# e-ink-display-v010.net
KiCad netlist of a schematic drawn in EAGLE
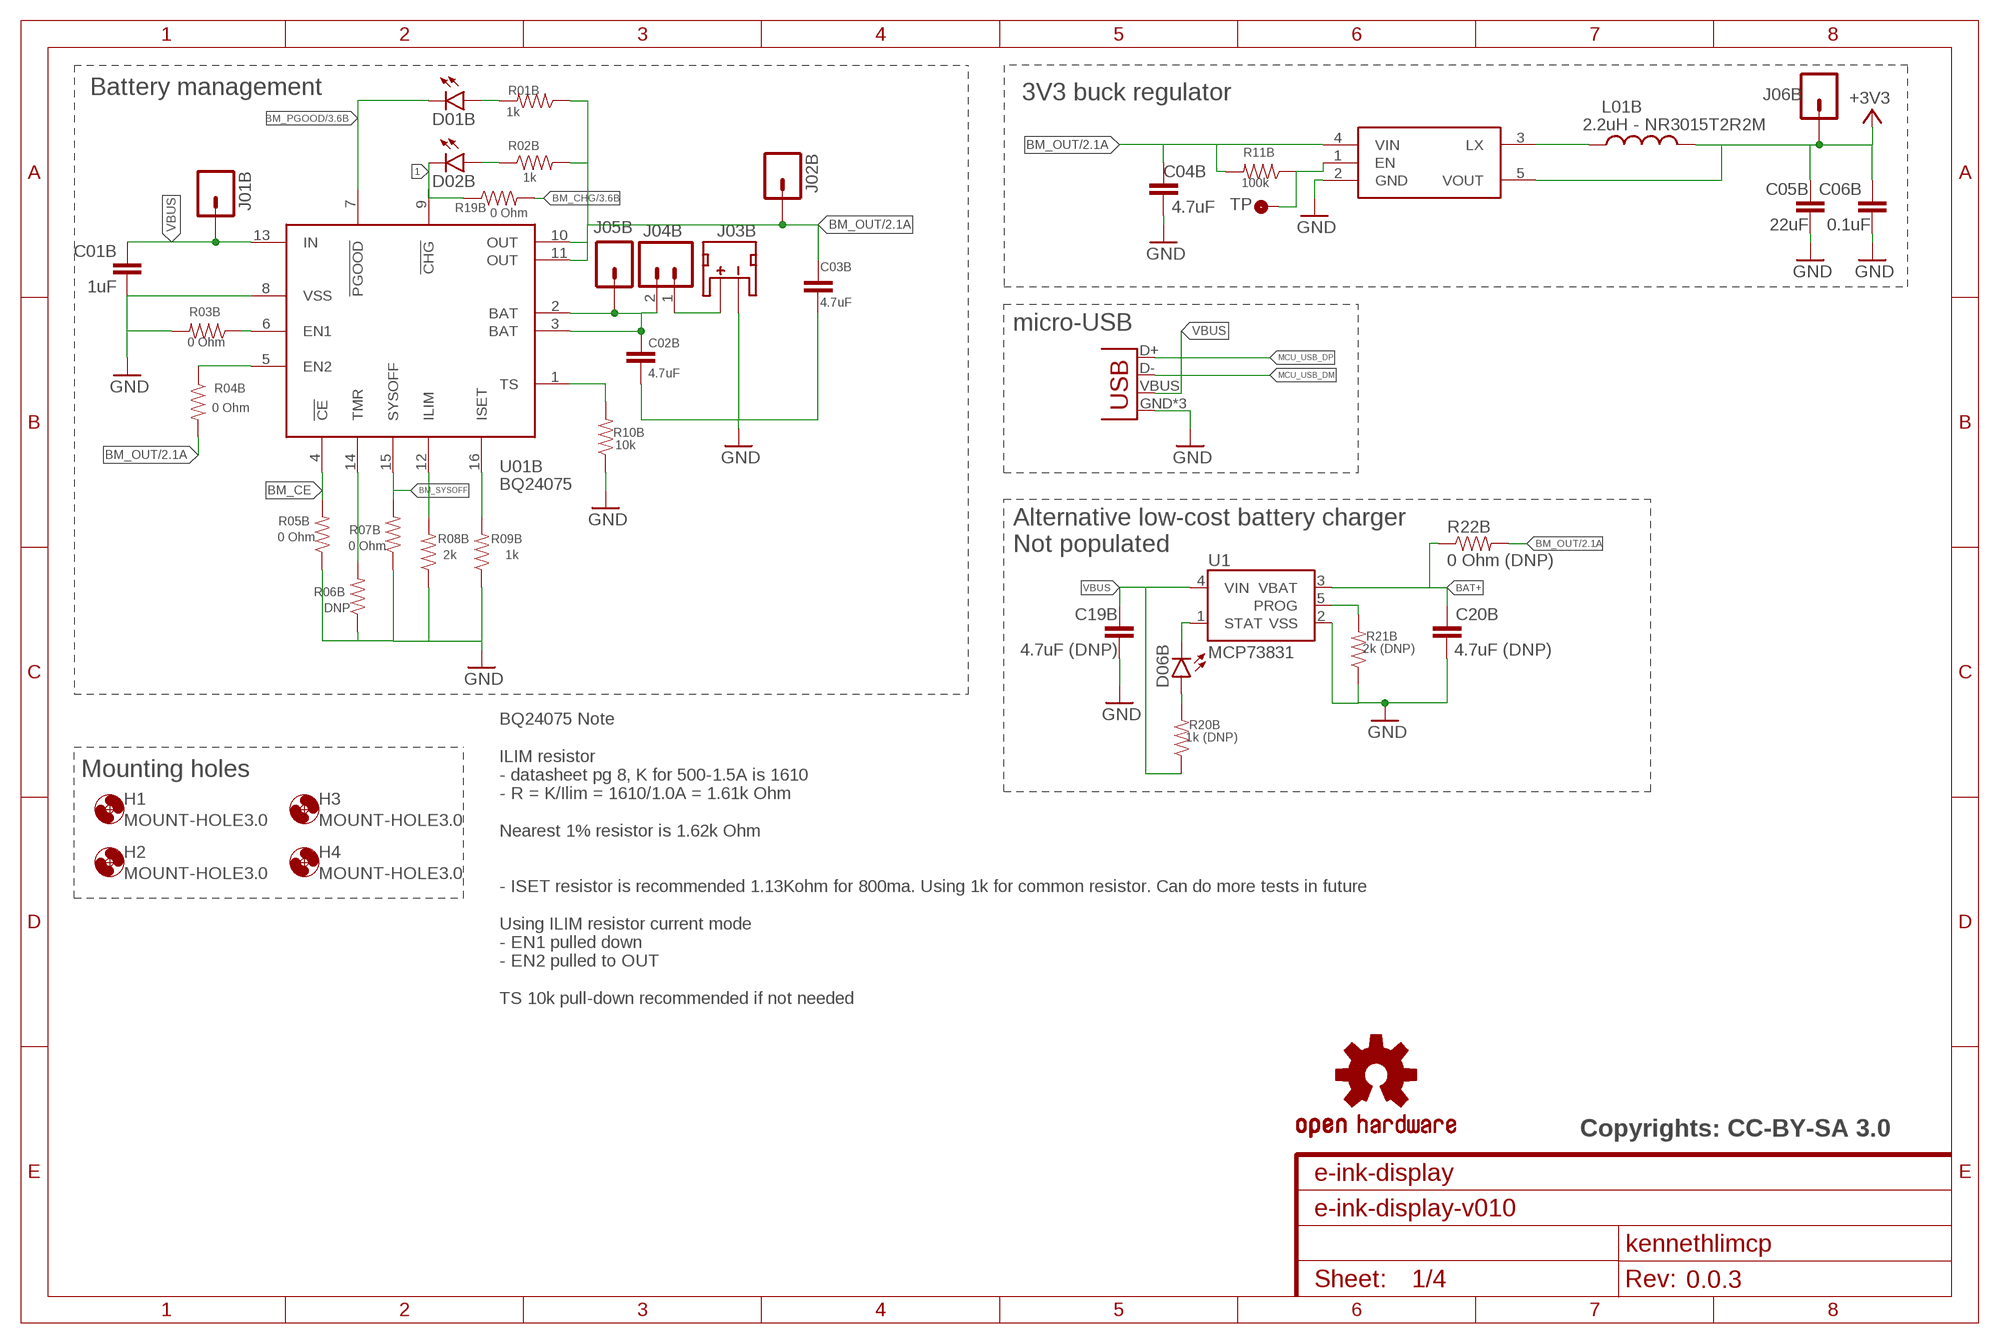
[diagram p0: schematic, sheet 1]
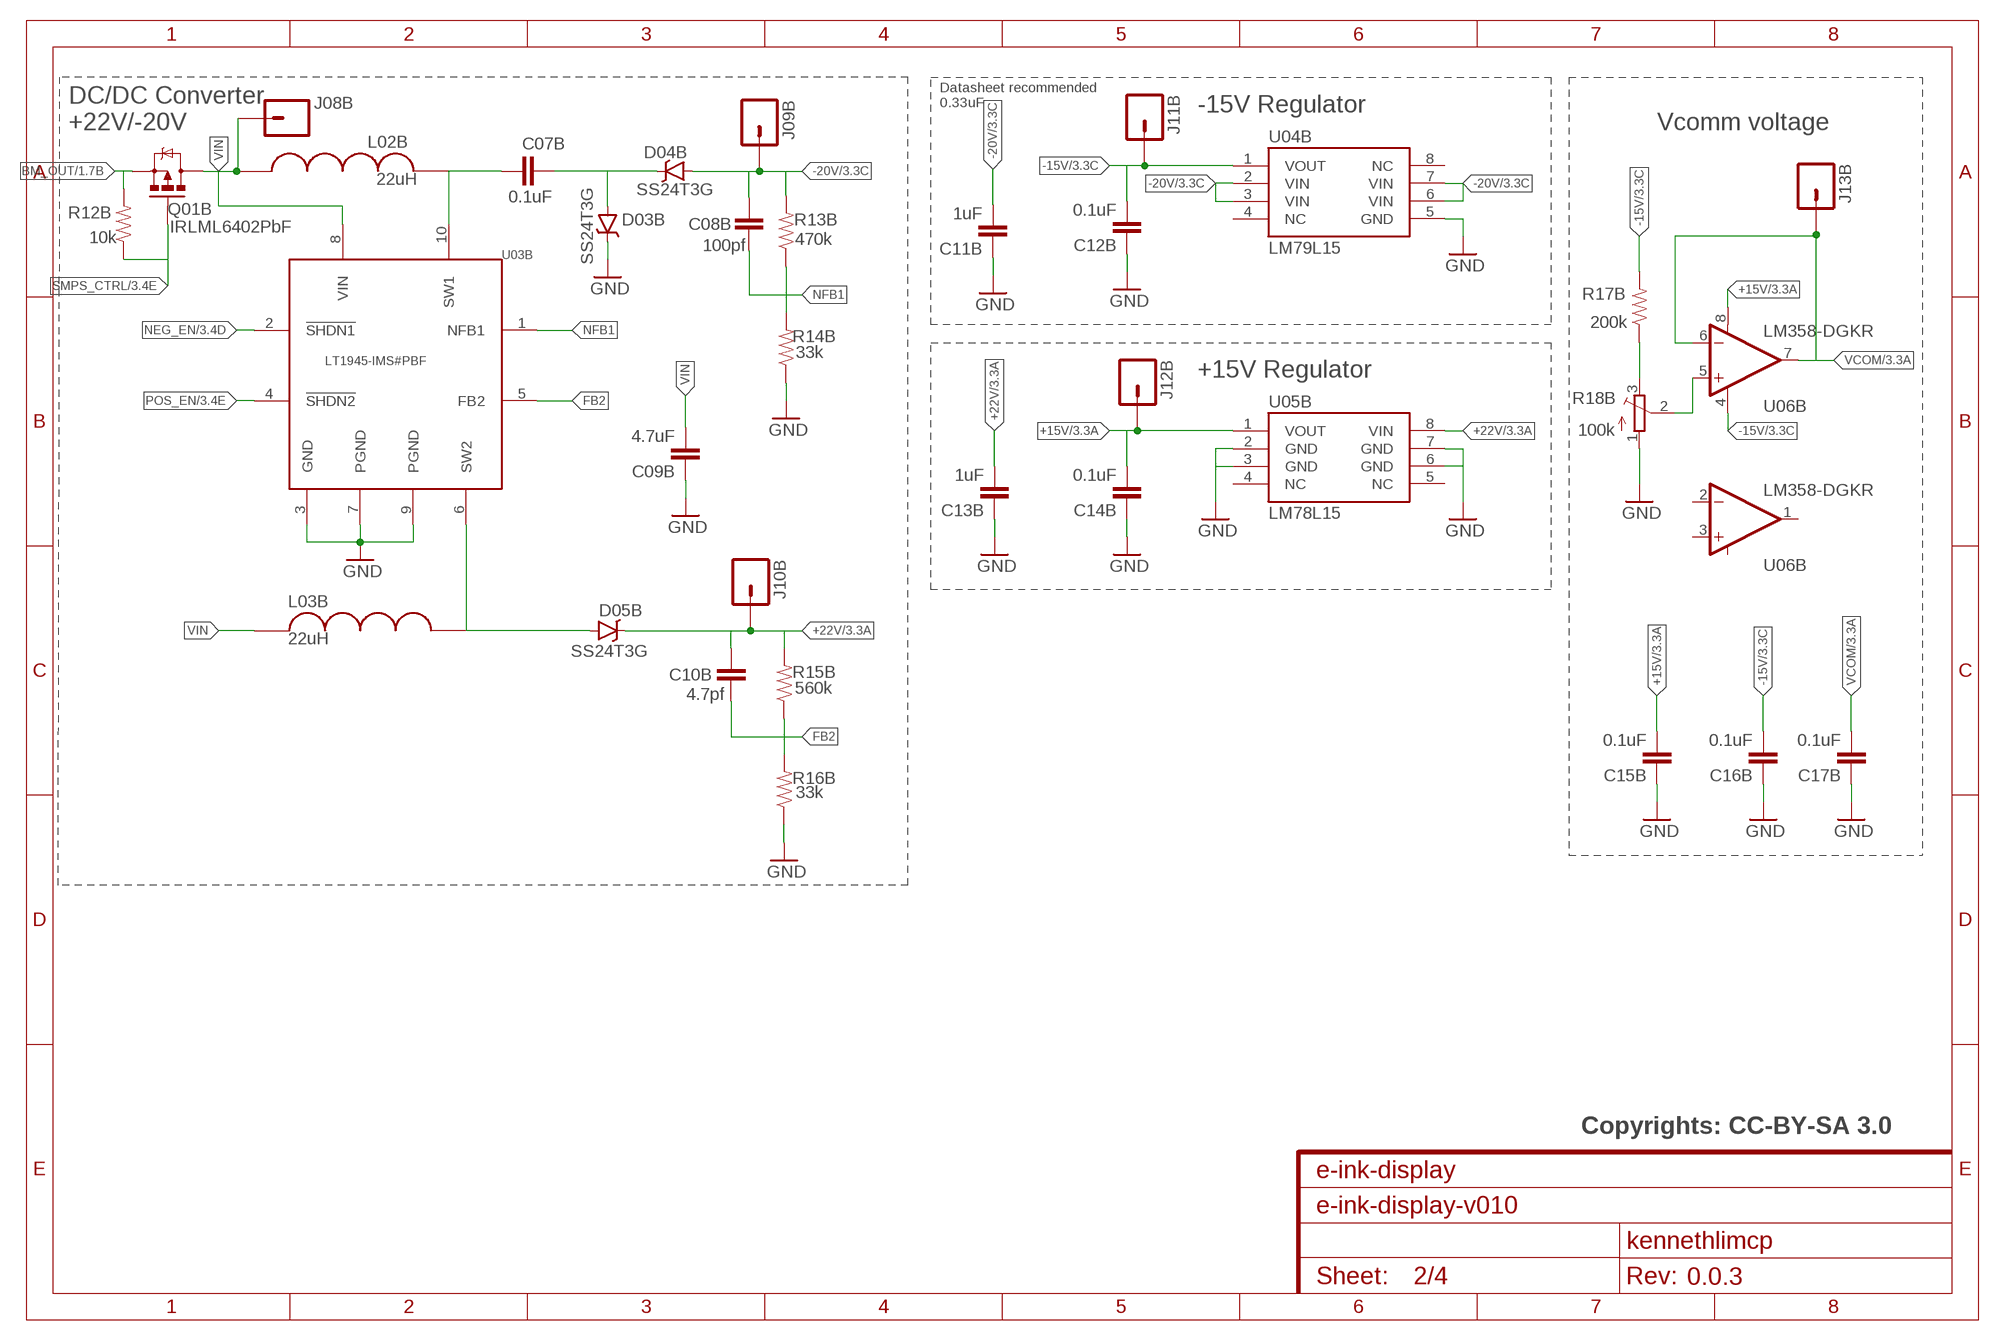
[diagram p1: schematic, sheet 2]
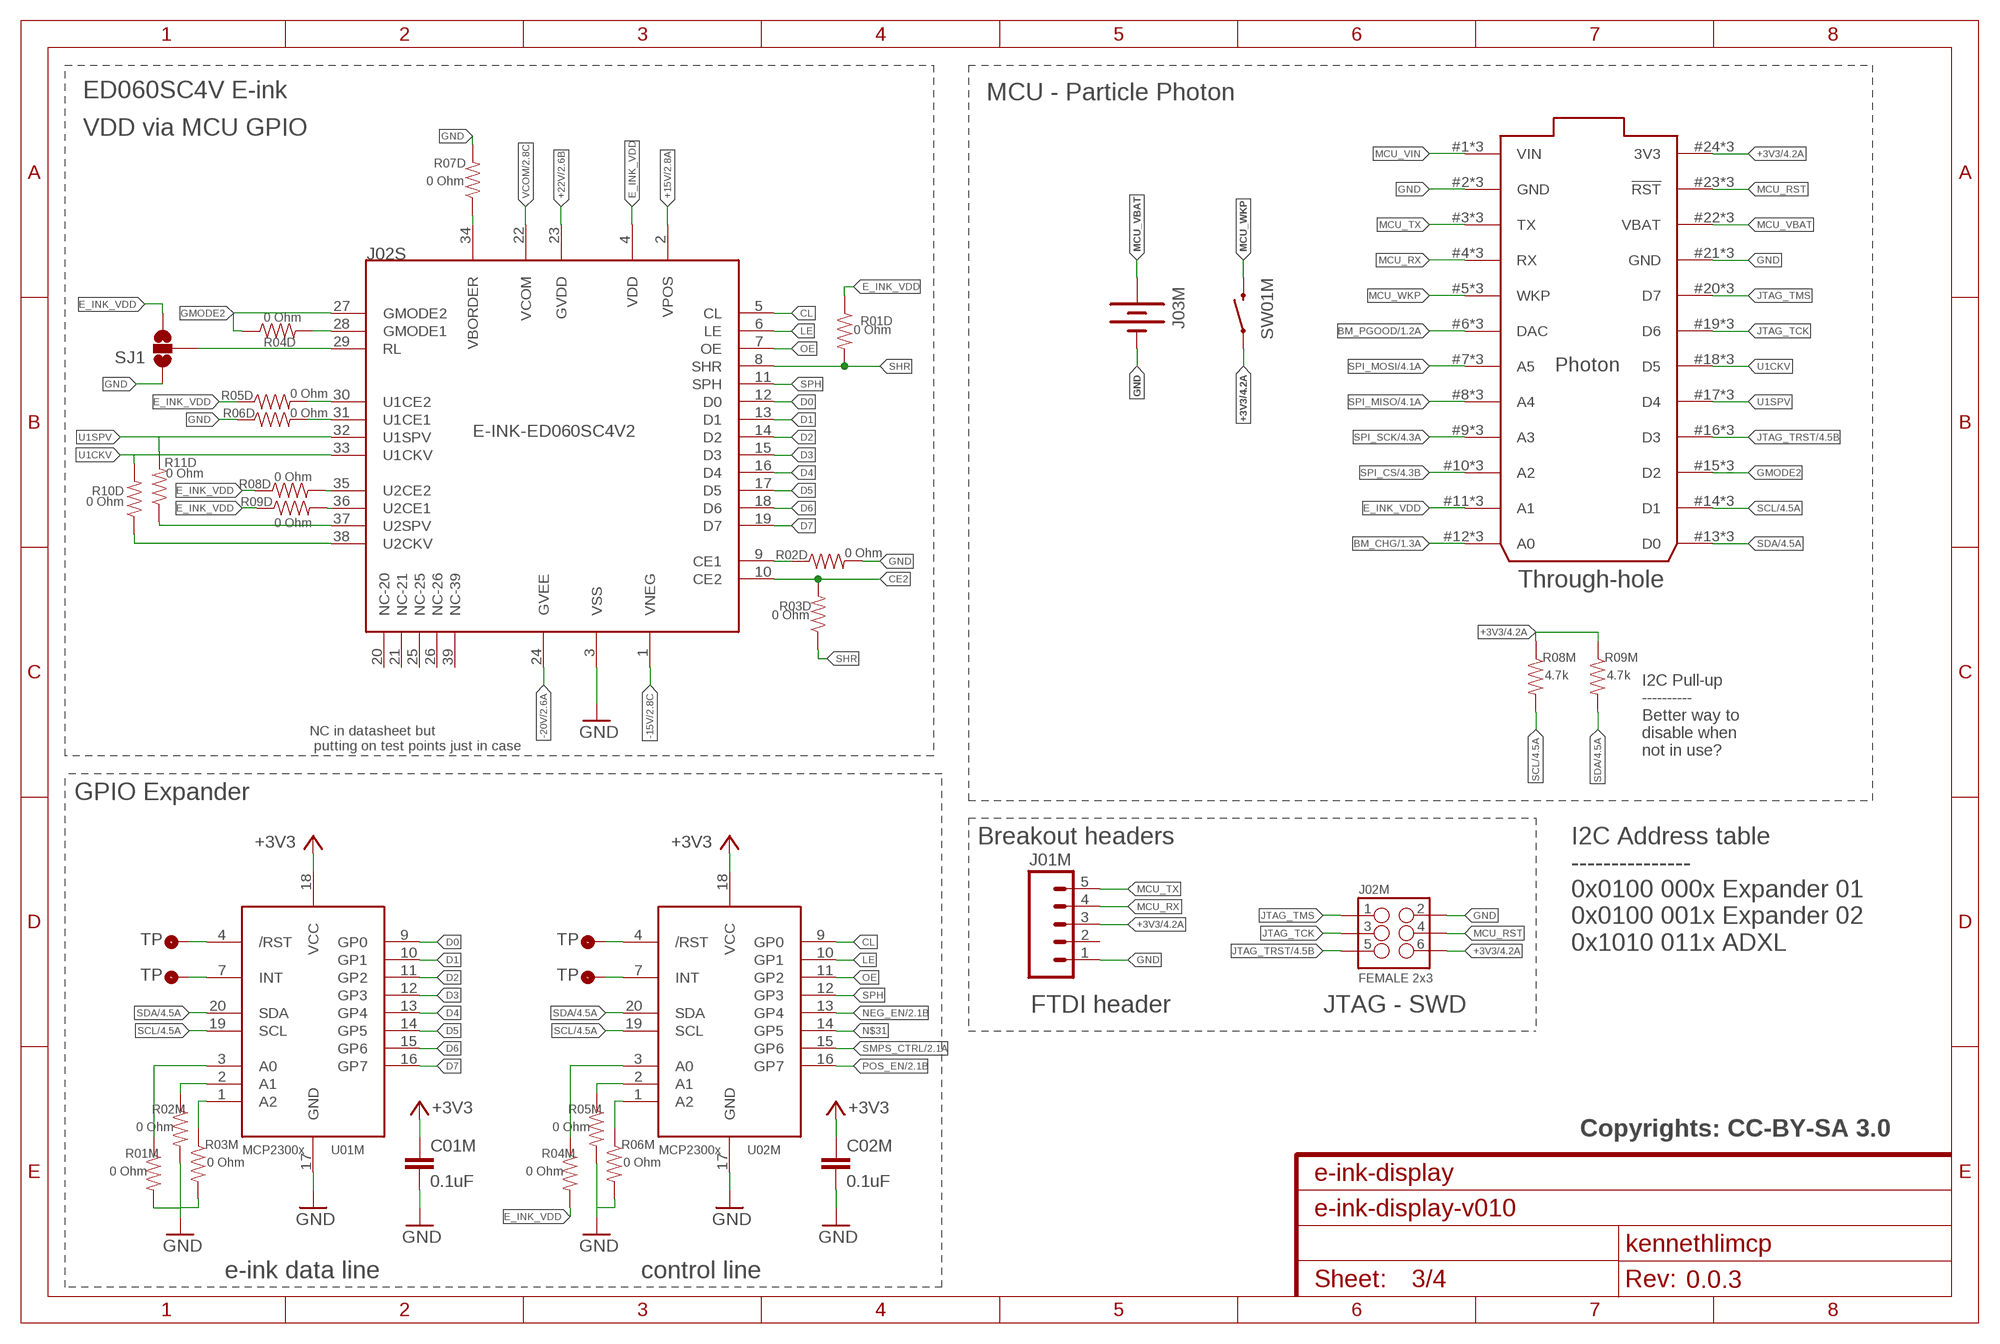
[diagram p2: schematic, sheet 3]
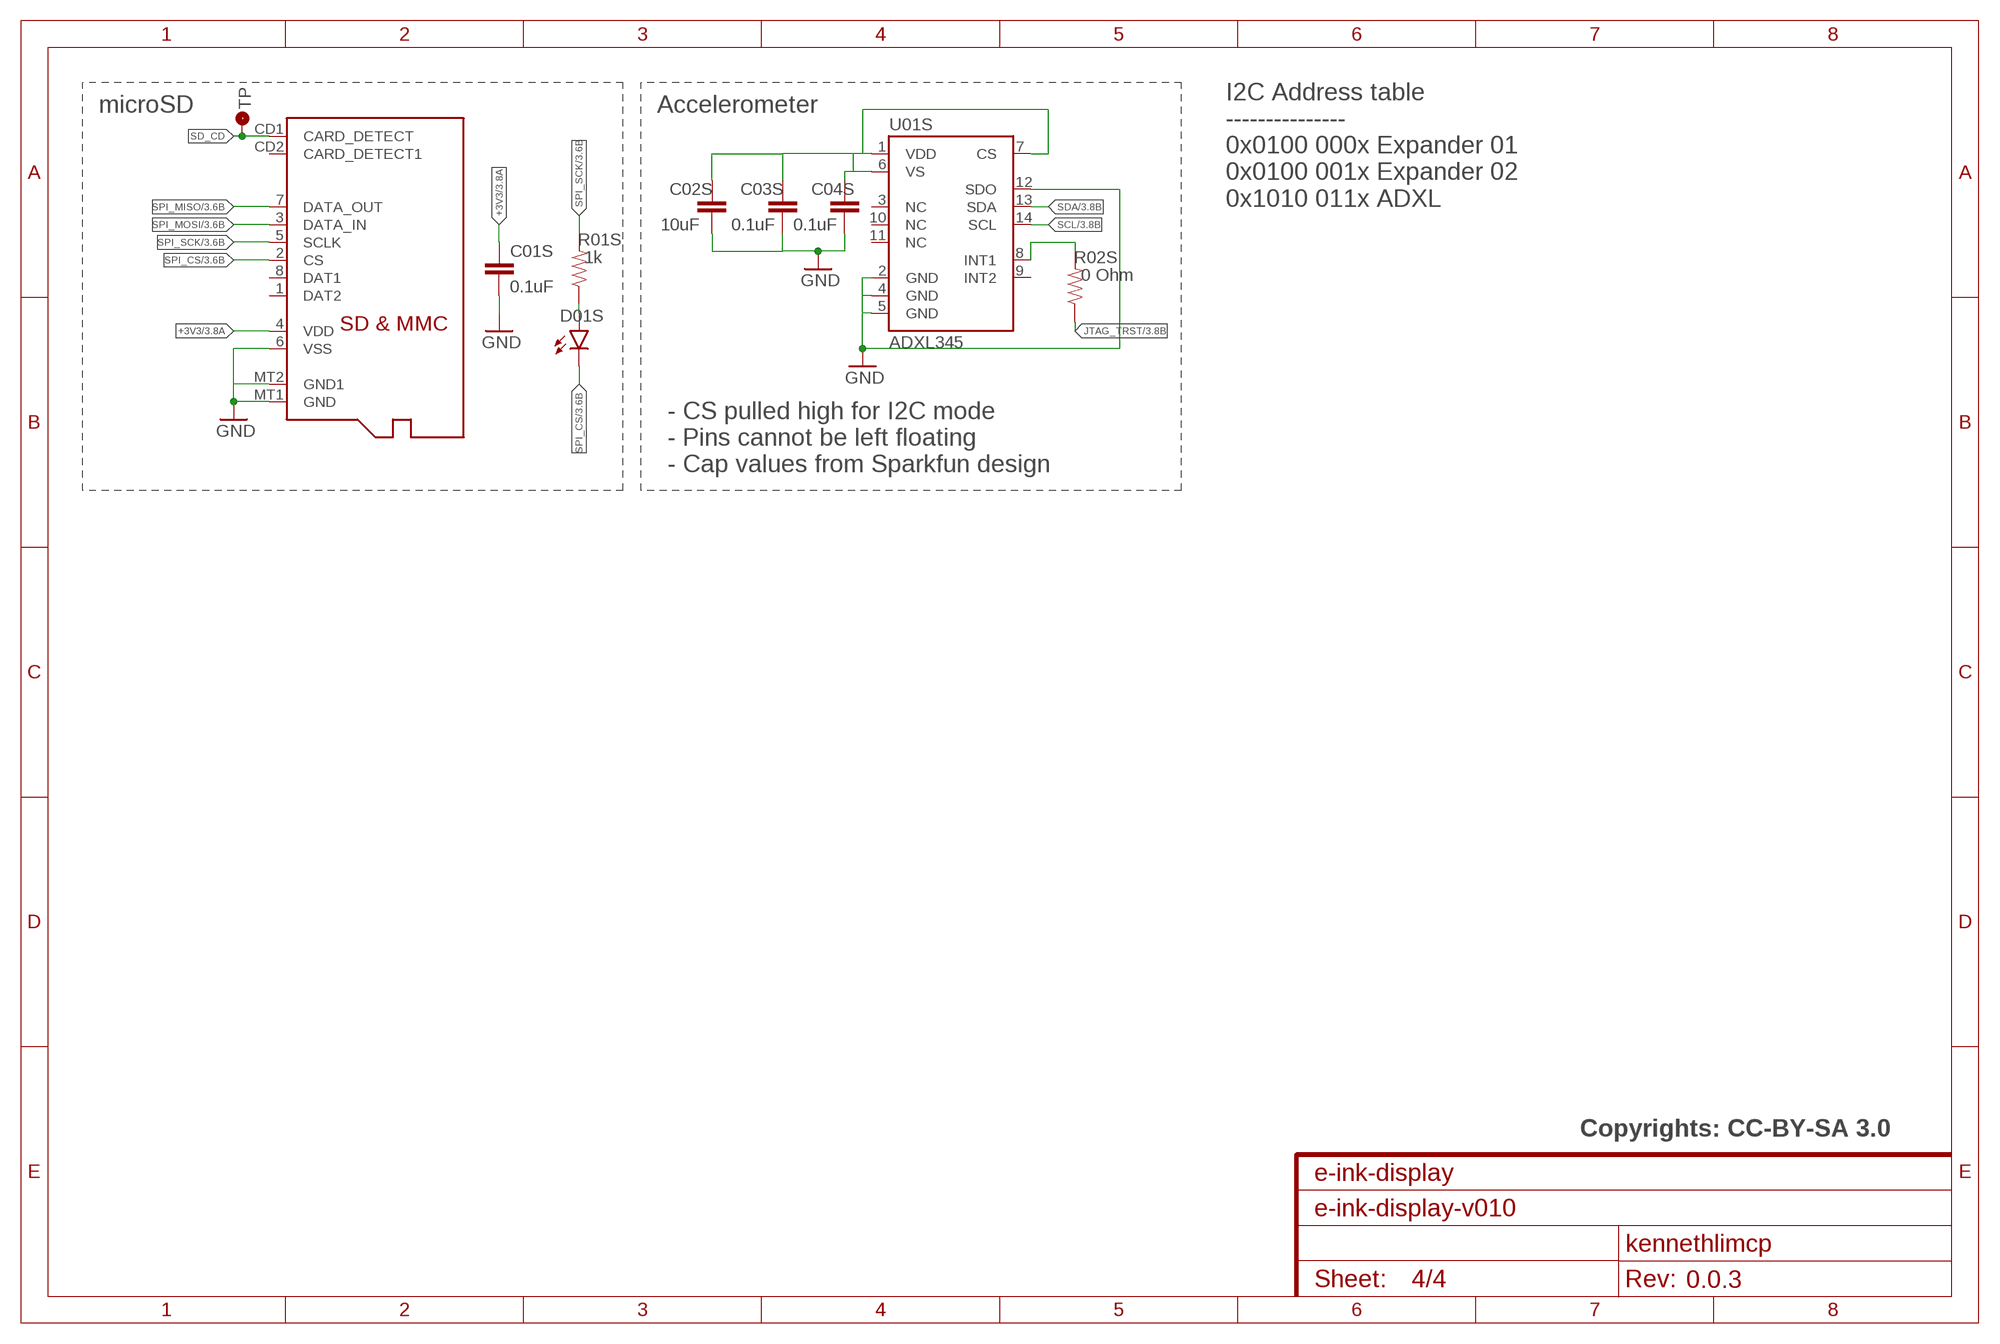
[diagram p3: schematic, sheet 4]

(export (version "E")
  (design (tool "Eeschema 10.0.6"))
  (components
    (comp (ref "C01B")
      (value "1uF")
      (footprint "eagle-import:0603-CAP")
      (libsource (lib "eagle-import") (part "CAP0603-CAP"))
    )
    (comp (ref "C02B")
      (value "4.7uF")
      (footprint "eagle-import:0603-CAP")
      (libsource (lib "eagle-import") (part "CAP0603-CAP"))
    )
    (comp (ref "C03B")
      (value "4.7uF")
      (footprint "eagle-import:0603-CAP")
      (libsource (lib "eagle-import") (part "CAP0603-CAP"))
    )
    (comp (ref "C04B")
      (value "4.7uF")
      (footprint "eagle-import:0603-CAP")
      (libsource (lib "eagle-import") (part "CAP0603-CAP"))
    )
    (comp (ref "C05B")
      (value "22uF")
      (footprint "eagle-import:0603-CAP")
      (libsource (lib "eagle-import") (part "CAP0603-CAP"))
    )
    (comp (ref "C06B")
      (value "0.1uF")
      (footprint "eagle-import:0603-CAP")
      (libsource (lib "eagle-import") (part "CAP0603-CAP"))
    )
    (comp (ref "C19B")
      (value "4.7uF (DNP)")
      (footprint "eagle-import:0603-CAP")
      (libsource (lib "eagle-import") (part "CAP0603-CAP"))
    )
    (comp (ref "C20B")
      (value "4.7uF (DNP)")
      (footprint "eagle-import:0603-CAP")
      (libsource (lib "eagle-import") (part "CAP0603-CAP"))
    )
    (comp (ref "D01B")
      (value "LED0603")
      (footprint "eagle-import:LED-0603")
      (libsource (lib "eagle-import") (part "LED0603"))
    )
    (comp (ref "D02B")
      (value "LED0603")
      (footprint "eagle-import:LED-0603")
      (libsource (lib "eagle-import") (part "LED0603"))
    )
    (comp (ref "D06B")
      (value "LED0603")
      (footprint "eagle-import:LED-0603")
      (libsource (lib "eagle-import") (part "LED0603"))
    )
    (comp (ref "H1")
      (value "MOUNT-HOLE3.0")
      (footprint "eagle-import:3,0")
      (libsource (lib "eagle-import") (part "MOUNT-HOLE3.0"))
    )
    (comp (ref "H2")
      (value "MOUNT-HOLE3.0")
      (footprint "eagle-import:3,0")
      (libsource (lib "eagle-import") (part "MOUNT-HOLE3.0"))
    )
    (comp (ref "H3")
      (value "MOUNT-HOLE3.0")
      (footprint "eagle-import:3,0")
      (libsource (lib "eagle-import") (part "MOUNT-HOLE3.0"))
    )
    (comp (ref "H4")
      (value "MOUNT-HOLE3.0")
      (footprint "eagle-import:3,0")
      (libsource (lib "eagle-import") (part "MOUNT-HOLE3.0"))
    )
    (comp (ref "J01B")
      (value "M01PTH")
      (footprint "eagle-import:1X01")
      (libsource (lib "eagle-import") (part "M01PTH"))
    )
    (comp (ref "J02B")
      (value "M01PTH")
      (footprint "eagle-import:1X01")
      (libsource (lib "eagle-import") (part "M01PTH"))
    )
    (comp (ref "J03B")
      (value "JST_2MM_MALE")
      (footprint "eagle-import:JST-2-SMD")
      (libsource (lib "eagle-import") (part "JST_2MM_MALE"))
    )
    (comp (ref "J04B")
      (value "M02PTH")
      (footprint "eagle-import:1X02")
      (libsource (lib "eagle-import") (part "M02PTH"))
    )
    (comp (ref "J05B")
      (value "M01PTH")
      (footprint "eagle-import:1X01")
      (libsource (lib "eagle-import") (part "M01PTH"))
    )
    (comp (ref "J06B")
      (value "M01PTH")
      (footprint "eagle-import:1X01")
      (libsource (lib "eagle-import") (part "M01PTH"))
    )
    (comp (ref "J07B")
      (value "USBUSB-MICROB-SLOT-HOLE")
      (footprint "eagle-import:USB-MICROB-SLOT-HOLE")
      (libsource (lib "eagle-import") (part "USBUSB-MICROB-SLOT-HOLE"))
    )
    (comp (ref "L01B")
      (value "2.2uH - NR3015T2R2M")
      (footprint "eagle-import:INDUCTOR-NR3015")
      (libsource (lib "eagle-import") (part "INDUCTOR-SPARKFUNNR3015T4R7M"))
    )
    (comp (ref "LOGO1")
      (value "OSHW-LOGOPAD")
      (footprint "eagle-import:OSHW-LOGO-M-PAD")
      (libsource (lib "eagle-import") (part "OSHW-LOGOPAD"))
    )
    (comp (ref "R01B")
      (value "1k")
      (footprint "eagle-import:0603-RES")
      (libsource (lib "eagle-import") (part "SparkFun-Resistors_RESISTOR0603-RES"))
    )
    (comp (ref "R02B")
      (value "1k")
      (footprint "eagle-import:0603-RES")
      (libsource (lib "eagle-import") (part "SparkFun-Resistors_RESISTOR0603-RES"))
    )
    (comp (ref "R03B")
      (value "0 Ohm")
      (footprint "eagle-import:0603-RES")
      (libsource (lib "eagle-import") (part "SparkFun-Resistors_RESISTOR0603-RES"))
    )
    (comp (ref "R04B")
      (value "0 Ohm")
      (footprint "eagle-import:0603-RES")
      (libsource (lib "eagle-import") (part "RESISTOR0603"))
    )
    (comp (ref "R05B")
      (value "0 Ohm")
      (footprint "eagle-import:0603-RES")
      (libsource (lib "eagle-import") (part "RESISTOR0603"))
    )
    (comp (ref "R06B")
      (value "DNP")
      (footprint "eagle-import:0603-RES")
      (libsource (lib "eagle-import") (part "RESISTOR0603"))
    )
    (comp (ref "R07B")
      (value "0 Ohm")
      (footprint "eagle-import:0603-RES")
      (libsource (lib "eagle-import") (part "RESISTOR0603"))
    )
    (comp (ref "R08B")
      (value "2k")
      (footprint "eagle-import:0603-RES")
      (libsource (lib "eagle-import") (part "RESISTOR0603"))
    )
    (comp (ref "R09B")
      (value "1k")
      (footprint "eagle-import:0603-RES")
      (libsource (lib "eagle-import") (part "SparkFun-Resistors_RESISTOR0603-RES"))
    )
    (comp (ref "R10B")
      (value "10k")
      (footprint "eagle-import:0603-RES")
      (libsource (lib "eagle-import") (part "RESISTOR0603"))
    )
    (comp (ref "R11B")
      (value "100k")
      (footprint "eagle-import:0603-RES")
      (libsource (lib "eagle-import") (part "RESISTOR0603"))
    )
    (comp (ref "R19B")
      (value "0 Ohm")
      (footprint "eagle-import:0603-RES")
      (libsource (lib "eagle-import") (part "RESISTOR0603"))
    )
    (comp (ref "R20B")
      (value "1k (DNP)")
      (footprint "eagle-import:0603-RES")
      (libsource (lib "eagle-import") (part "RESISTOR0603"))
    )
    (comp (ref "R21B")
      (value "2k (DNP)")
      (footprint "eagle-import:0603-RES")
      (libsource (lib "eagle-import") (part "RESISTOR0603"))
    )
    (comp (ref "R22B")
      (value "0 Ohm (DNP)")
      (footprint "eagle-import:1206")
      (libsource (lib "eagle-import") (part "SparkFun-Resistors_RESISTOR1206"))
    )
    (comp (ref "TP01B")
      (value "TP1")
      (footprint "eagle-import:TP35_BOT")
      (libsource (lib "eagle-import") (part "TP1"))
    )
    (comp (ref "U1")
      (value "MCP73831")
      (footprint "eagle-import:SOT23-5")
      (libsource (lib "eagle-import") (part "MCP73831"))
    )
    (comp (ref "U01B")
      (value "BQ24075")
      (footprint "eagle-import:PVQFN-16")
      (libsource (lib "eagle-import") (part "BQ2407"))
    )
    (comp (ref "U02B")
      (value "R8008-33")
      (footprint "eagle-import:SOT23-5")
      (libsource (lib "eagle-import") (part "R8008-33"))
    )
    (comp (ref "C01S")
      (value "0.1uF")
      (footprint "eagle-import:0603-CAP")
      (libsource (lib "eagle-import") (part "CAP0603-CAP"))
    )
    (comp (ref "C02S")
      (value "10uF")
      (footprint "eagle-import:0603-CAP")
      (libsource (lib "eagle-import") (part "CAP0603-CAP"))
    )
    (comp (ref "C03S")
      (value "0.1uF")
      (footprint "eagle-import:0603-CAP")
      (libsource (lib "eagle-import") (part "CAP0603-CAP"))
    )
    (comp (ref "C04S")
      (value "0.1uF")
      (footprint "eagle-import:0603-CAP")
      (libsource (lib "eagle-import") (part "CAP0603-CAP"))
    )
    (comp (ref "D01S")
      (value "LED0603")
      (footprint "eagle-import:LED-0603")
      (libsource (lib "eagle-import") (part "LED0603"))
    )
    (comp (ref "J01S")
      (value "MICROSD")
      (footprint "eagle-import:MICROSD")
      (libsource (lib "eagle-import") (part "MICROSD"))
    )
    (comp (ref "R01S")
      (value "1k")
      (footprint "eagle-import:0603-RES")
      (libsource (lib "eagle-import") (part "SparkFun-Resistors_RESISTOR0603-RES"))
    )
    (comp (ref "R02S")
      (value "0 Ohm")
      (footprint "eagle-import:0603-RES")
      (libsource (lib "eagle-import") (part "RESISTOR0603"))
    )
    (comp (ref "U$5")
      (value "TP3")
      (footprint "eagle-import:TP60_BOT")
      (libsource (lib "eagle-import") (part "TP3"))
    )
    (comp (ref "U01S")
      (value "ADXL345")
      (footprint "eagle-import:LGA14")
      (libsource (lib "eagle-import") (part "ADXL345"))
    )
    (comp (ref "C01M")
      (value "0.1uF")
      (footprint "eagle-import:0603-CAP")
      (libsource (lib "eagle-import") (part "CAP0603-CAP"))
    )
    (comp (ref "C02M")
      (value "0.1uF")
      (footprint "eagle-import:0603-CAP")
      (libsource (lib "eagle-import") (part "CAP0603-CAP"))
    )
    (comp (ref "J01M")
      (value "M05PTH")
      (footprint "eagle-import:1X05")
      (libsource (lib "eagle-import") (part "M05PTH"))
    )
    (comp (ref "J02M")
      (value "FEMALE 2x3")
      (footprint "eagle-import:2X3")
      (libsource (lib "eagle-import") (part "M03X2FEMALE"))
    )
    (comp (ref "J02S")
      (value "E-INK-ED060SC4V2")
      (footprint "eagle-import:FPC-0.3-39")
      (libsource (lib "eagle-import") (part "E-INK-ED060SC4V2"))
    )
    (comp (ref "J03M")
      (value "BATTERY20PTH")
      (footprint "eagle-import:BATTCOM_20MM_PTH")
      (libsource (lib "eagle-import") (part "BATTERY20PTH"))
    )
    (comp (ref "R01D")
      (value "0 Ohm")
      (footprint "eagle-import:0603-RES")
      (libsource (lib "eagle-import") (part "RESISTOR0603-RES"))
    )
    (comp (ref "R01M")
      (value "0 Ohm")
      (footprint "eagle-import:0603-RES")
      (libsource (lib "eagle-import") (part "RESISTOR0603-RES"))
    )
    (comp (ref "R02D")
      (value "0 Ohm")
      (footprint "eagle-import:0603-RES")
      (libsource (lib "eagle-import") (part "RESISTOR0603-RES"))
    )
    (comp (ref "R02M")
      (value "0 Ohm")
      (footprint "eagle-import:0603-RES")
      (libsource (lib "eagle-import") (part "RESISTOR0603-RES"))
    )
    (comp (ref "R03D")
      (value "0 Ohm")
      (footprint "eagle-import:0603-RES")
      (libsource (lib "eagle-import") (part "RESISTOR0603-RES"))
    )
    (comp (ref "R03M")
      (value "0 Ohm")
      (footprint "eagle-import:0603-RES")
      (libsource (lib "eagle-import") (part "RESISTOR0603-RES"))
    )
    (comp (ref "R04D")
      (value "0 Ohm")
      (footprint "eagle-import:0603-RES")
      (libsource (lib "eagle-import") (part "RESISTOR0603-RES"))
    )
    (comp (ref "R04M")
      (value "0 Ohm")
      (footprint "eagle-import:0603-RES")
      (libsource (lib "eagle-import") (part "RESISTOR0603-RES"))
    )
    (comp (ref "R05D")
      (value "0 Ohm")
      (footprint "eagle-import:0603-RES")
      (libsource (lib "eagle-import") (part "RESISTOR0603-RES"))
    )
    (comp (ref "R05M")
      (value "0 Ohm")
      (footprint "eagle-import:0603-RES")
      (libsource (lib "eagle-import") (part "RESISTOR0603-RES"))
    )
    (comp (ref "R06D")
      (value "0 Ohm")
      (footprint "eagle-import:0603-RES")
      (libsource (lib "eagle-import") (part "RESISTOR0603-RES"))
    )
    (comp (ref "R06M")
      (value "0 Ohm")
      (footprint "eagle-import:0603-RES")
      (libsource (lib "eagle-import") (part "RESISTOR0603-RES"))
    )
    (comp (ref "R07D")
      (value "0 Ohm")
      (footprint "eagle-import:0603-RES")
      (libsource (lib "eagle-import") (part "RESISTOR0603-RES"))
    )
    (comp (ref "R08D")
      (value "0 Ohm")
      (footprint "eagle-import:0603-RES")
      (libsource (lib "eagle-import") (part "RESISTOR0603-RES"))
    )
    (comp (ref "R08M")
      (value "4.7k")
      (footprint "eagle-import:0603-RES")
      (libsource (lib "eagle-import") (part "RESISTOR0603-RES"))
    )
    (comp (ref "R09D")
      (value "0 Ohm")
      (footprint "eagle-import:0603-RES")
      (libsource (lib "eagle-import") (part "RESISTOR0603-RES"))
    )
    (comp (ref "R09M")
      (value "4.7k")
      (footprint "eagle-import:0603-RES")
      (libsource (lib "eagle-import") (part "RESISTOR0603-RES"))
    )
    (comp (ref "R10D")
      (value "0 Ohm")
      (footprint "eagle-import:0603-RES")
      (libsource (lib "eagle-import") (part "RESISTOR0603-RES"))
    )
    (comp (ref "R11D")
      (value "0 Ohm")
      (footprint "eagle-import:0603-RES")
      (libsource (lib "eagle-import") (part "RESISTOR0603-RES"))
    )
    (comp (ref "SJ1")
      (value "SOLDERJUMPER_2WAYT")
      (footprint "eagle-import:SJ_2")
      (libsource (lib "eagle-import") (part "SOLDERJUMPER_2WAYT"))
    )
    (comp (ref "SW01M")
      (value "SWITCH-MOMENTARY-2PTH")
      (footprint "eagle-import:TACTILE-PTH")
      (libsource (lib "eagle-import") (part "SWITCH-MOMENTARY-2PTH"))
    )
    (comp (ref "U$1")
      (value "TP1")
      (footprint "eagle-import:TP35_BOT")
      (libsource (lib "eagle-import") (part "TP1"))
    )
    (comp (ref "U$2")
      (value "TP1")
      (footprint "eagle-import:TP35_BOT")
      (libsource (lib "eagle-import") (part "TP1"))
    )
    (comp (ref "U$3")
      (value "TP1")
      (footprint "eagle-import:TP35_BOT")
      (libsource (lib "eagle-import") (part "TP1"))
    )
    (comp (ref "U$4")
      (value "TP1")
      (footprint "eagle-import:TP35_BOT")
      (libsource (lib "eagle-import") (part "TP1"))
    )
    (comp (ref "U01M")
      (value "MCP2300X/QFN")
      (footprint "eagle-import:QFN-20(4X4)")
      (libsource (lib "eagle-import") (part "MCP2300X/QFN"))
    )
    (comp (ref "U02M")
      (value "MCP2300X/QFN")
      (footprint "eagle-import:QFN-20(4X4)")
      (libsource (lib "eagle-import") (part "MCP2300X/QFN"))
    )
    (comp (ref "U03M")
      (value "PHOTON_WITH_STACKABLE_HEADERS")
      (footprint "eagle-import:PHOTON_STACKABLE")
      (libsource (lib "eagle-import") (part "PHOTON_WITH_STACKABLE_HEADERS"))
    )
    (comp (ref "C07B")
      (value "0.1uF")
      (footprint "eagle-import:0603-CAP")
      (libsource (lib "eagle-import") (part "CAP0603-CAP"))
    )
    (comp (ref "C08B")
      (value "100pf")
      (footprint "eagle-import:0603-CAP")
      (libsource (lib "eagle-import") (part "CAP0603-CAP"))
    )
    (comp (ref "C09B")
      (value "4.7uF")
      (footprint "eagle-import:0603-CAP")
      (libsource (lib "eagle-import") (part "CAP0603-CAP"))
    )
    (comp (ref "C10B")
      (value "4.7pf")
      (footprint "eagle-import:0603-CAP")
      (libsource (lib "eagle-import") (part "CAP0603-CAP"))
    )
    (comp (ref "C11B")
      (value "1uF")
      (footprint "eagle-import:0603-CAP")
      (libsource (lib "eagle-import") (part "CAP0603-CAP"))
    )
    (comp (ref "C12B")
      (value "0.1uF")
      (footprint "eagle-import:0603-CAP")
      (libsource (lib "eagle-import") (part "CAP0603-CAP"))
    )
    (comp (ref "C13B")
      (value "1uF")
      (footprint "eagle-import:0603-CAP")
      (libsource (lib "eagle-import") (part "CAP0603-CAP"))
    )
    (comp (ref "C14B")
      (value "0.1uF")
      (footprint "eagle-import:0603-CAP")
      (libsource (lib "eagle-import") (part "CAP0603-CAP"))
    )
    (comp (ref "C15B")
      (value "0.1uF")
      (footprint "eagle-import:0603-CAP")
      (libsource (lib "eagle-import") (part "CAP0603-CAP"))
    )
    (comp (ref "C16B")
      (value "0.1uF")
      (footprint "eagle-import:0603-CAP")
      (libsource (lib "eagle-import") (part "CAP0603-CAP"))
    )
    (comp (ref "C17B")
      (value "0.1uF")
      (footprint "eagle-import:0603-CAP")
      (libsource (lib "eagle-import") (part "CAP0603-CAP"))
    )
    (comp (ref "D03B")
      (value "SS24T3G")
      (footprint "eagle-import:SMA-DIODE")
      (libsource (lib "eagle-import") (part "SS24T3G"))
    )
    (comp (ref "D04B")
      (value "SS24T3G")
      (footprint "eagle-import:SMA-DIODE")
      (libsource (lib "eagle-import") (part "SS24T3G"))
    )
    (comp (ref "D05B")
      (value "SS24T3G")
      (footprint "eagle-import:SMA-DIODE")
      (libsource (lib "eagle-import") (part "SS24T3G"))
    )
    (comp (ref "J08B")
      (value "M01PTH")
      (footprint "eagle-import:1X01")
      (libsource (lib "eagle-import") (part "M01PTH"))
    )
    (comp (ref "J09B")
      (value "M01PTH")
      (footprint "eagle-import:1X01")
      (libsource (lib "eagle-import") (part "M01PTH"))
    )
    (comp (ref "J10B")
      (value "M01PTH")
      (footprint "eagle-import:1X01")
      (libsource (lib "eagle-import") (part "M01PTH"))
    )
    (comp (ref "J11B")
      (value "M01PTH")
      (footprint "eagle-import:1X01")
      (libsource (lib "eagle-import") (part "M01PTH"))
    )
    (comp (ref "J12B")
      (value "M01PTH")
      (footprint "eagle-import:1X01")
      (libsource (lib "eagle-import") (part "M01PTH"))
    )
    (comp (ref "J13B")
      (value "M01PTH")
      (footprint "eagle-import:1X01")
      (libsource (lib "eagle-import") (part "M01PTH"))
    )
    (comp (ref "L02B")
      (value "22uH")
      (footprint "eagle-import:4040(1515)")
      (libsource (lib "eagle-import") (part "INDUCTOR"))
    )
    (comp (ref "L03B")
      (value "22uH")
      (footprint "eagle-import:4040(1515)")
      (libsource (lib "eagle-import") (part "INDUCTOR"))
    )
    (comp (ref "Q01B")
      (value "IRLML6402PbF")
      (footprint "eagle-import:SOT23-3")
      (libsource (lib "eagle-import") (part "MOSFET-PCHANNELSMD"))
    )
    (comp (ref "R12B")
      (value "10k")
      (footprint "eagle-import:0603-RES")
      (libsource (lib "eagle-import") (part "RESISTOR0603"))
    )
    (comp (ref "R13B")
      (value "470k")
      (footprint "eagle-import:0603-RES")
      (libsource (lib "eagle-import") (part "RESISTOR0603"))
    )
    (comp (ref "R14B")
      (value "33k")
      (footprint "eagle-import:0603-RES")
      (libsource (lib "eagle-import") (part "RESISTOR0603"))
    )
    (comp (ref "R15B")
      (value "560k")
      (footprint "eagle-import:0603-RES")
      (libsource (lib "eagle-import") (part "RESISTOR0603"))
    )
    (comp (ref "R16B")
      (value "33k")
      (footprint "eagle-import:0603-RES")
      (libsource (lib "eagle-import") (part "RESISTOR0603"))
    )
    (comp (ref "R17B")
      (value "200k")
      (footprint "eagle-import:0603-RES")
      (libsource (lib "eagle-import") (part "RESISTOR0603"))
    )
    (comp (ref "R18B")
      (value "100k")
      (footprint "eagle-import:TC33X")
      (libsource (lib "eagle-import") (part "TRIMPOTTC33X"))
    )
    (comp (ref "U03B")
      (value "LT1945-IMS#PBF")
      (footprint "eagle-import:MSOP-10")
      (libsource (lib "eagle-import") (part "LT1945-IMS#PBF"))
    )
    (comp (ref "U04B")
      (value "LM79L15")
      (footprint "eagle-import:SO08")
      (libsource (lib "eagle-import") (part "LM79L15"))
    )
    (comp (ref "U05B")
      (value "LM78L15")
      (footprint "eagle-import:SO08")
      (libsource (lib "eagle-import") (part "LM78L15"))
    )
    (comp (ref "U06B")
      (value "LM358-DGKR")
      (footprint "eagle-import:MSOP-8")
      (libsource (lib "eagle-import") (part "LM358-DGKR"))
    )
  )
  (nets
    (net (code "1") (name "+3V3") (class "Default")
      (node (ref "C01M") (pin "1") (pinfunction "1_1") (pintype "passive"))
      (node (ref "C01S") (pin "1") (pinfunction "1_1") (pintype "passive"))
      (node (ref "C02M") (pin "1") (pinfunction "1_1") (pintype "passive"))
      (node (ref "C05B") (pin "2") (pinfunction "2_2") (pintype "passive"))
      (node (ref "C06B") (pin "2") (pinfunction "2_2") (pintype "passive"))
      (node (ref "J01M") (pin "3") (pinfunction "3_3") (pintype "passive"))
      (node (ref "J01S") (pin "4") (pinfunction "VDD_4") (pintype "power_in"))
      (node (ref "J02M") (pin "6") (pinfunction "6_6") (pintype "bidirectional"))
      (node (ref "J06B") (pin "1") (pinfunction "1_1") (pintype "passive"))
      (node (ref "L01B") (pin "2") (pinfunction "2_2") (pintype "passive"))
      (node (ref "R08M") (pin "1") (pinfunction "1_1") (pintype "passive"))
      (node (ref "R09M") (pin "1") (pinfunction "1_1") (pintype "passive"))
      (node (ref "SW01M") (pin "1") (pinfunction "1_1") (pintype "passive"))
      (node (ref "U01M") (pin "18") (pinfunction "VCC_18") (pintype "power_in"))
      (node (ref "U02B") (pin "5") (pinfunction "VOUT_5") (pintype "bidirectional"))
      (node (ref "U02M") (pin "18") (pinfunction "VCC_18") (pintype "power_in"))
      (node (ref "U03M") (pin "#24") (pinfunction "3V3_#24") (pintype "power_in"))
      (node (ref "U03M") (pin "24") (pinfunction "3V3_24") (pintype "power_in"))
      (node (ref "U03M") (pin "@24") (pinfunction "3V3_@24") (pintype "power_in"))
    )
    (net (code "2") (name "+15V") (class "Default")
      (node (ref "C14B") (pin "2") (pinfunction "2_2") (pintype "passive"))
      (node (ref "C15B") (pin "2") (pinfunction "2_2") (pintype "passive"))
      (node (ref "J02S") (pin "2") (pinfunction "VPOS_2") (pintype "bidirectional"))
      (node (ref "J12B") (pin "1") (pinfunction "1_1") (pintype "passive"))
      (node (ref "U05B") (pin "1") (pinfunction "VOUT_1") (pintype "bidirectional"))
      (node (ref "U06B") (pin "8") (pinfunction "V+_8") (pintype "power_in"))
    )
    (net (code "3") (name "+22V") (class "Default")
      (node (ref "C10B") (pin "2") (pinfunction "2_2") (pintype "passive"))
      (node (ref "C13B") (pin "2") (pinfunction "2_2") (pintype "passive"))
      (node (ref "D05B") (pin "C") (pinfunction "C_C") (pintype "passive"))
      (node (ref "J02S") (pin "23") (pinfunction "GVDD_23") (pintype "bidirectional"))
      (node (ref "J10B") (pin "1") (pinfunction "1_1") (pintype "passive"))
      (node (ref "R15B") (pin "2") (pinfunction "2_2") (pintype "passive"))
      (node (ref "U05B") (pin "8") (pinfunction "VIN_8") (pintype "bidirectional"))
    )
    (net (code "4") (name "-15V") (class "Default")
      (node (ref "C12B") (pin "2") (pinfunction "2_2") (pintype "passive"))
      (node (ref "C16B") (pin "2") (pinfunction "2_2") (pintype "passive"))
      (node (ref "J02S") (pin "1") (pinfunction "VNEG_1") (pintype "bidirectional"))
      (node (ref "J11B") (pin "1") (pinfunction "1_1") (pintype "passive"))
      (node (ref "R17B") (pin "2") (pinfunction "2_2") (pintype "passive"))
      (node (ref "U04B") (pin "1") (pinfunction "VOUT_1") (pintype "bidirectional"))
      (node (ref "U06B") (pin "4") (pinfunction "V-_4") (pintype "power_in"))
    )
    (net (code "5") (name "-20V") (class "Default")
      (node (ref "C08B") (pin "2") (pinfunction "2_2") (pintype "passive"))
      (node (ref "C11B") (pin "2") (pinfunction "2_2") (pintype "passive"))
      (node (ref "D04B") (pin "A") (pinfunction "A_A") (pintype "passive"))
      (node (ref "J02S") (pin "24") (pinfunction "GVEE_24") (pintype "bidirectional"))
      (node (ref "J09B") (pin "1") (pinfunction "1_1") (pintype "passive"))
      (node (ref "R13B") (pin "2") (pinfunction "2_2") (pintype "passive"))
      (node (ref "U04B") (pin "2") (pinfunction "VIN_2") (pintype "bidirectional"))
      (node (ref "U04B") (pin "3") (pinfunction "VIN_3") (pintype "bidirectional"))
      (node (ref "U04B") (pin "6") (pinfunction "VIN_6") (pintype "bidirectional"))
      (node (ref "U04B") (pin "7") (pinfunction "VIN_7") (pintype "bidirectional"))
    )
    (net (code "6") (name "1") (class "Default")
      (node (ref "D02B") (pin "C") (pinfunction "C_C") (pintype "passive"))
      (node (ref "R19B") (pin "1") (pinfunction "1_1") (pintype "passive"))
      (node (ref "U01B") (pin "9") (pinfunction "~{CHG}_9") (pintype "bidirectional"))
    )
    (net (code "7") (name "BAT+") (class "Default")
      (node (ref "C20B") (pin "2") (pinfunction "2_2") (pintype "passive"))
      (node (ref "J03B") (pin "2") (pinfunction "+_2") (pintype "bidirectional"))
      (node (ref "J04B") (pin "1") (pinfunction "1_1") (pintype "passive"))
      (node (ref "R22B") (pin "1") (pinfunction "1_1") (pintype "passive"))
      (node (ref "U1") (pin "3") (pinfunction "VBAT_3") (pintype "power_in"))
    )
    (net (code "8") (name "BM_CE") (class "Default")
      (node (ref "R05B") (pin "2") (pinfunction "2_2") (pintype "passive"))
      (node (ref "U01B") (pin "4") (pinfunction "~{CE}_4") (pintype "bidirectional"))
    )
    (net (code "9") (name "BM_CHG") (class "Default")
      (node (ref "R19B") (pin "2") (pinfunction "2_2") (pintype "passive"))
      (node (ref "U03M") (pin "#12") (pinfunction "A0_#12") (pintype "bidirectional"))
      (node (ref "U03M") (pin "12") (pinfunction "A0_12") (pintype "bidirectional"))
      (node (ref "U03M") (pin "@12") (pinfunction "A0_@12") (pintype "bidirectional"))
    )
    (net (code "10") (name "BM_OUT") (class "Default")
      (node (ref "C03B") (pin "2") (pinfunction "2_2") (pintype "passive"))
      (node (ref "C04B") (pin "2") (pinfunction "2_2") (pintype "passive"))
      (node (ref "J02B") (pin "1") (pinfunction "1_1") (pintype "passive"))
      (node (ref "Q01B") (pin "2") (pinfunction "S_2") (pintype "passive"))
      (node (ref "R01B") (pin "1") (pinfunction "1_1") (pintype "passive"))
      (node (ref "R02B") (pin "2") (pinfunction "2_2") (pintype "passive"))
      (node (ref "R04B") (pin "2") (pinfunction "2_2") (pintype "passive"))
      (node (ref "R11B") (pin "2") (pinfunction "2_2") (pintype "passive"))
      (node (ref "R12B") (pin "2") (pinfunction "2_2") (pintype "passive"))
      (node (ref "R22B") (pin "2") (pinfunction "2_2") (pintype "passive"))
      (node (ref "U01B") (pin "10") (pinfunction "OUT_10") (pintype "bidirectional"))
      (node (ref "U01B") (pin "11") (pinfunction "OUT_11") (pintype "bidirectional"))
      (node (ref "U02B") (pin "4") (pinfunction "VIN_4") (pintype "bidirectional"))
    )
    (net (code "11") (name "BM_PGOOD") (class "Default")
      (node (ref "D01B") (pin "C") (pinfunction "C_C") (pintype "passive"))
      (node (ref "U01B") (pin "7") (pinfunction "~{PGOOD}_7") (pintype "bidirectional"))
      (node (ref "U03M") (pin "#6") (pinfunction "DAC_#6") (pintype "bidirectional"))
      (node (ref "U03M") (pin "6") (pinfunction "DAC_6") (pintype "bidirectional"))
      (node (ref "U03M") (pin "@6") (pinfunction "DAC_@6") (pintype "bidirectional"))
    )
    (net (code "12") (name "BM_SYSOFF") (class "Default")
      (node (ref "R07B") (pin "2") (pinfunction "2_2") (pintype "passive"))
      (node (ref "U01B") (pin "15") (pinfunction "SYSOFF_15") (pintype "bidirectional"))
    )
    (net (code "13") (name "CE2") (class "Default")
      (node (ref "J02S") (pin "10") (pinfunction "CE2_10") (pintype "bidirectional"))
      (node (ref "R03D") (pin "2") (pinfunction "2_2") (pintype "passive"))
    )
    (net (code "14") (name "CL") (class "Default")
      (node (ref "J02S") (pin "5") (pinfunction "CL_5") (pintype "bidirectional"))
      (node (ref "U02M") (pin "9") (pinfunction "GP0_9") (pintype "bidirectional"))
    )
    (net (code "15") (name "D0") (class "Default")
      (node (ref "J02S") (pin "12") (pinfunction "D0_12") (pintype "bidirectional"))
      (node (ref "U01M") (pin "9") (pinfunction "GP0_9") (pintype "bidirectional"))
    )
    (net (code "16") (name "D1") (class "Default")
      (node (ref "J02S") (pin "13") (pinfunction "D1_13") (pintype "bidirectional"))
      (node (ref "U01M") (pin "10") (pinfunction "GP1_10") (pintype "bidirectional"))
    )
    (net (code "17") (name "D2") (class "Default")
      (node (ref "J02S") (pin "14") (pinfunction "D2_14") (pintype "bidirectional"))
      (node (ref "U01M") (pin "11") (pinfunction "GP2_11") (pintype "bidirectional"))
    )
    (net (code "18") (name "D3") (class "Default")
      (node (ref "J02S") (pin "15") (pinfunction "D3_15") (pintype "bidirectional"))
      (node (ref "U01M") (pin "12") (pinfunction "GP3_12") (pintype "bidirectional"))
    )
    (net (code "19") (name "D4") (class "Default")
      (node (ref "J02S") (pin "16") (pinfunction "D4_16") (pintype "bidirectional"))
      (node (ref "U01M") (pin "13") (pinfunction "GP4_13") (pintype "bidirectional"))
    )
    (net (code "20") (name "D5") (class "Default")
      (node (ref "J02S") (pin "17") (pinfunction "D5_17") (pintype "bidirectional"))
      (node (ref "U01M") (pin "14") (pinfunction "GP5_14") (pintype "bidirectional"))
    )
    (net (code "21") (name "D6") (class "Default")
      (node (ref "J02S") (pin "18") (pinfunction "D6_18") (pintype "bidirectional"))
      (node (ref "U01M") (pin "15") (pinfunction "GP6_15") (pintype "bidirectional"))
    )
    (net (code "22") (name "D7") (class "Default")
      (node (ref "J02S") (pin "19") (pinfunction "D7_19") (pintype "bidirectional"))
      (node (ref "U01M") (pin "16") (pinfunction "GP7_16") (pintype "bidirectional"))
    )
    (net (code "23") (name "E_INK_VDD") (class "Default")
      (node (ref "J02S") (pin "4") (pinfunction "VDD_4") (pintype "bidirectional"))
      (node (ref "R01D") (pin "1") (pinfunction "1_1") (pintype "passive"))
      (node (ref "R04M") (pin "2") (pinfunction "2_2") (pintype "passive"))
      (node (ref "R05D") (pin "1") (pinfunction "1_1") (pintype "passive"))
      (node (ref "R08D") (pin "1") (pinfunction "1_1") (pintype "passive"))
      (node (ref "R09D") (pin "1") (pinfunction "1_1") (pintype "passive"))
      (node (ref "SJ1") (pin "3") (pinfunction "3_3") (pintype "passive"))
      (node (ref "U03M") (pin "#11") (pinfunction "A1_#11") (pintype "bidirectional"))
      (node (ref "U03M") (pin "11") (pinfunction "A1_11") (pintype "bidirectional"))
      (node (ref "U03M") (pin "@11") (pinfunction "A1_@11") (pintype "bidirectional"))
    )
    (net (code "24") (name "FB2") (class "Default")
      (node (ref "C10B") (pin "1") (pinfunction "1_1") (pintype "passive"))
      (node (ref "R15B") (pin "1") (pinfunction "1_1") (pintype "passive"))
      (node (ref "R16B") (pin "2") (pinfunction "2_2") (pintype "passive"))
      (node (ref "U03B") (pin "5") (pinfunction "FB2_5") (pintype "bidirectional"))
    )
    (net (code "25") (name "GMODE2") (class "Default")
      (node (ref "J02S") (pin "27") (pinfunction "GMODE2_27") (pintype "bidirectional"))
      (node (ref "R04D") (pin "1") (pinfunction "1_1") (pintype "passive"))
      (node (ref "U03M") (pin "#15") (pinfunction "D2_#15") (pintype "bidirectional"))
      (node (ref "U03M") (pin "15") (pinfunction "D2_15") (pintype "bidirectional"))
      (node (ref "U03M") (pin "@15") (pinfunction "D2_@15") (pintype "bidirectional"))
    )
    (net (code "26") (name "GND") (class "Default")
      (node (ref "C01B") (pin "1") (pinfunction "1_1") (pintype "passive"))
      (node (ref "C01M") (pin "2") (pinfunction "2_2") (pintype "passive"))
      (node (ref "C01S") (pin "2") (pinfunction "2_2") (pintype "passive"))
      (node (ref "C02B") (pin "1") (pinfunction "1_1") (pintype "passive"))
      (node (ref "C02M") (pin "2") (pinfunction "2_2") (pintype "passive"))
      (node (ref "C02S") (pin "2") (pinfunction "2_2") (pintype "passive"))
      (node (ref "C03B") (pin "1") (pinfunction "1_1") (pintype "passive"))
      (node (ref "C03S") (pin "2") (pinfunction "2_2") (pintype "passive"))
      (node (ref "C04B") (pin "1") (pinfunction "1_1") (pintype "passive"))
      (node (ref "C04S") (pin "2") (pinfunction "2_2") (pintype "passive"))
      (node (ref "C05B") (pin "1") (pinfunction "1_1") (pintype "passive"))
      (node (ref "C06B") (pin "1") (pinfunction "1_1") (pintype "passive"))
      (node (ref "C09B") (pin "1") (pinfunction "1_1") (pintype "passive"))
      (node (ref "C11B") (pin "1") (pinfunction "1_1") (pintype "passive"))
      (node (ref "C12B") (pin "1") (pinfunction "1_1") (pintype "passive"))
      (node (ref "C13B") (pin "1") (pinfunction "1_1") (pintype "passive"))
      (node (ref "C14B") (pin "1") (pinfunction "1_1") (pintype "passive"))
      (node (ref "C15B") (pin "1") (pinfunction "1_1") (pintype "passive"))
      (node (ref "C16B") (pin "1") (pinfunction "1_1") (pintype "passive"))
      (node (ref "C17B") (pin "1") (pinfunction "1_1") (pintype "passive"))
      (node (ref "C19B") (pin "1") (pinfunction "1_1") (pintype "passive"))
      (node (ref "C20B") (pin "1") (pinfunction "1_1") (pintype "passive"))
      (node (ref "D03B") (pin "C") (pinfunction "C_C") (pintype "passive"))
      (node (ref "J01M") (pin "1") (pinfunction "1_1") (pintype "passive"))
      (node (ref "J01S") (pin "6") (pinfunction "VSS_6") (pintype "power_in"))
      (node (ref "J01S") (pin "MT1") (pinfunction "GND_MT1") (pintype "power_in"))
      (node (ref "J01S") (pin "MT2") (pinfunction "GND1_MT2") (pintype "power_in"))
      (node (ref "J02M") (pin "2") (pinfunction "2_2") (pintype "bidirectional"))
      (node (ref "J02S") (pin "3") (pinfunction "VSS_3") (pintype "bidirectional"))
      (node (ref "J03B") (pin "1") (pinfunction "-_1") (pintype "bidirectional"))
      (node (ref "J03M") (pin "2") (pinfunction "-_2") (pintype "power_in"))
      (node (ref "J07B") (pin "GND") (pinfunction "GND_GND") (pintype "bidirectional"))
      (node (ref "J07B") (pin "MT1") (pinfunction "GND_MT1") (pintype "bidirectional"))
      (node (ref "J07B") (pin "MT2") (pinfunction "GND_MT2") (pintype "bidirectional"))
      (node (ref "R01M") (pin "2") (pinfunction "2_2") (pintype "passive"))
      (node (ref "R02D") (pin "2") (pinfunction "2_2") (pintype "passive"))
      (node (ref "R02M") (pin "2") (pinfunction "2_2") (pintype "passive"))
      (node (ref "R03B") (pin "2") (pinfunction "2_2") (pintype "passive"))
      (node (ref "R03M") (pin "2") (pinfunction "2_2") (pintype "passive"))
      (node (ref "R05B") (pin "1") (pinfunction "1_1") (pintype "passive"))
      (node (ref "R05M") (pin "2") (pinfunction "2_2") (pintype "passive"))
      (node (ref "R06B") (pin "1") (pinfunction "1_1") (pintype "passive"))
      (node (ref "R06D") (pin "1") (pinfunction "1_1") (pintype "passive"))
      (node (ref "R06M") (pin "2") (pinfunction "2_2") (pintype "passive"))
      (node (ref "R07B") (pin "1") (pinfunction "1_1") (pintype "passive"))
      (node (ref "R07D") (pin "2") (pinfunction "2_2") (pintype "passive"))
      (node (ref "R08B") (pin "1") (pinfunction "1_1") (pintype "passive"))
      (node (ref "R09B") (pin "1") (pinfunction "1_1") (pintype "passive"))
      (node (ref "R10B") (pin "1") (pinfunction "1_1") (pintype "passive"))
      (node (ref "R14B") (pin "1") (pinfunction "1_1") (pintype "passive"))
      (node (ref "R16B") (pin "1") (pinfunction "1_1") (pintype "passive"))
      (node (ref "R18B") (pin "1") (pinfunction "A_1") (pintype "passive"))
      (node (ref "R21B") (pin "1") (pinfunction "1_1") (pintype "passive"))
      (node (ref "SJ1") (pin "1") (pinfunction "1_1") (pintype "passive"))
      (node (ref "U01B") (pin "8") (pinfunction "VSS_8") (pintype "bidirectional"))
      (node (ref "U01M") (pin "17") (pinfunction "GND_17") (pintype "power_in"))
      (node (ref "U01S") (pin "12") (pinfunction "SDO_12") (pintype "bidirectional"))
      (node (ref "U01S") (pin "2") (pinfunction "GND_2") (pintype "bidirectional"))
      (node (ref "U01S") (pin "4") (pinfunction "GND_4") (pintype "bidirectional"))
      (node (ref "U01S") (pin "5") (pinfunction "GND_5") (pintype "bidirectional"))
      (node (ref "U02B") (pin "2") (pinfunction "GND_2") (pintype "bidirectional"))
      (node (ref "U02M") (pin "17") (pinfunction "GND_17") (pintype "power_in"))
      (node (ref "U03B") (pin "3") (pinfunction "GND_3") (pintype "bidirectional"))
      (node (ref "U03B") (pin "7") (pinfunction "PGND_7") (pintype "bidirectional"))
      (node (ref "U03B") (pin "9") (pinfunction "PGND_9") (pintype "bidirectional"))
      (node (ref "U03M") (pin "#2") (pinfunction "GND_#2") (pintype "power_in"))
      (node (ref "U03M") (pin "#21") (pinfunction "GND_#21") (pintype "power_in"))
      (node (ref "U03M") (pin "2") (pinfunction "GND_2") (pintype "power_in"))
      (node (ref "U03M") (pin "21") (pinfunction "GND_21") (pintype "power_in"))
      (node (ref "U03M") (pin "@2") (pinfunction "GND_@2") (pintype "power_in"))
      (node (ref "U03M") (pin "@21") (pinfunction "GND_@21") (pintype "power_in"))
      (node (ref "U04B") (pin "5") (pinfunction "GND_5") (pintype "bidirectional"))
      (node (ref "U05B") (pin "2") (pinfunction "GND_2") (pintype "bidirectional"))
      (node (ref "U05B") (pin "3") (pinfunction "GND_3") (pintype "bidirectional"))
      (node (ref "U05B") (pin "6") (pinfunction "GND_6") (pintype "bidirectional"))
      (node (ref "U05B") (pin "7") (pinfunction "GND_7") (pintype "bidirectional"))
      (node (ref "U1") (pin "2") (pinfunction "VSS_2") (pintype "power_in"))
    )
    (net (code "27") (name "JTAG_TCK") (class "Default")
      (node (ref "J02M") (pin "3") (pinfunction "3_3") (pintype "bidirectional"))
      (node (ref "U03M") (pin "#19") (pinfunction "D6_#19") (pintype "bidirectional"))
      (node (ref "U03M") (pin "19") (pinfunction "D6_19") (pintype "bidirectional"))
      (node (ref "U03M") (pin "@19") (pinfunction "D6_@19") (pintype "bidirectional"))
    )
    (net (code "28") (name "JTAG_TMS") (class "Default")
      (node (ref "J02M") (pin "1") (pinfunction "1_1") (pintype "bidirectional"))
      (node (ref "U03M") (pin "#20") (pinfunction "D7_#20") (pintype "bidirectional"))
      (node (ref "U03M") (pin "20") (pinfunction "D7_20") (pintype "bidirectional"))
      (node (ref "U03M") (pin "@20") (pinfunction "D7_@20") (pintype "bidirectional"))
    )
    (net (code "29") (name "JTAG_TRST") (class "Default")
      (node (ref "J02M") (pin "5") (pinfunction "5_5") (pintype "bidirectional"))
      (node (ref "R02S") (pin "1") (pinfunction "1_1") (pintype "passive"))
      (node (ref "U03M") (pin "#16") (pinfunction "D3_#16") (pintype "bidirectional"))
      (node (ref "U03M") (pin "16") (pinfunction "D3_16") (pintype "bidirectional"))
      (node (ref "U03M") (pin "@16") (pinfunction "D3_@16") (pintype "bidirectional"))
    )
    (net (code "30") (name "LE") (class "Default")
      (node (ref "J02S") (pin "6") (pinfunction "LE_6") (pintype "bidirectional"))
      (node (ref "U02M") (pin "10") (pinfunction "GP1_10") (pintype "bidirectional"))
    )
    (net (code "31") (name "MCU_RST") (class "Default")
      (node (ref "J02M") (pin "4") (pinfunction "4_4") (pintype "bidirectional"))
      (node (ref "U03M") (pin "#23") (pinfunction "~{RST}_#23") (pintype "bidirectional"))
      (node (ref "U03M") (pin "23") (pinfunction "~{RST}_23") (pintype "bidirectional"))
      (node (ref "U03M") (pin "@23") (pinfunction "~{RST}_@23") (pintype "bidirectional"))
    )
    (net (code "32") (name "MCU_RX") (class "Default")
      (node (ref "J01M") (pin "4") (pinfunction "4_4") (pintype "passive"))
      (node (ref "U03M") (pin "#4") (pinfunction "RX_#4") (pintype "bidirectional"))
      (node (ref "U03M") (pin "4") (pinfunction "RX_4") (pintype "bidirectional"))
      (node (ref "U03M") (pin "@4") (pinfunction "RX_@4") (pintype "bidirectional"))
    )
    (net (code "33") (name "MCU_TX") (class "Default")
      (node (ref "J01M") (pin "5") (pinfunction "5_5") (pintype "passive"))
      (node (ref "U03M") (pin "#3") (pinfunction "TX_#3") (pintype "bidirectional"))
      (node (ref "U03M") (pin "3") (pinfunction "TX_3") (pintype "bidirectional"))
      (node (ref "U03M") (pin "@3") (pinfunction "TX_@3") (pintype "bidirectional"))
    )
    (net (code "34") (name "MCU_USB_DM") (class "Default")
      (node (ref "J07B") (pin "D-") (pinfunction "D-_D-") (pintype "bidirectional"))
    )
    (net (code "35") (name "MCU_USB_DP") (class "Default")
      (node (ref "J07B") (pin "D+") (pinfunction "D+_D+") (pintype "bidirectional"))
    )
    (net (code "36") (name "MCU_VBAT") (class "Default")
      (node (ref "J03M") (pin "1") (pinfunction "+_1") (pintype "power_in"))
      (node (ref "U03M") (pin "#22") (pinfunction "VBAT_#22") (pintype "power_in"))
      (node (ref "U03M") (pin "22") (pinfunction "VBAT_22") (pintype "power_in"))
      (node (ref "U03M") (pin "@22") (pinfunction "VBAT_@22") (pintype "power_in"))
    )
    (net (code "37") (name "MCU_VIN") (class "Default")
      (node (ref "U03M") (pin "#1") (pinfunction "VIN_#1") (pintype "power_in"))
      (node (ref "U03M") (pin "1") (pinfunction "VIN_1") (pintype "power_in"))
      (node (ref "U03M") (pin "@1") (pinfunction "VIN_@1") (pintype "power_in"))
    )
    (net (code "38") (name "MCU_WKP") (class "Default")
      (node (ref "SW01M") (pin "3") (pinfunction "2_3") (pintype "passive"))
      (node (ref "U03M") (pin "#5") (pinfunction "WKP_#5") (pintype "bidirectional"))
      (node (ref "U03M") (pin "5") (pinfunction "WKP_5") (pintype "bidirectional"))
      (node (ref "U03M") (pin "@5") (pinfunction "WKP_@5") (pintype "bidirectional"))
    )
    (net (code "39") (name "N$31") (class "Default")
      (node (ref "U02M") (pin "14") (pinfunction "GP5_14") (pintype "bidirectional"))
    )
    (net (code "40") (name "NEG_EN") (class "Default")
      (node (ref "U02M") (pin "13") (pinfunction "GP4_13") (pintype "bidirectional"))
      (node (ref "U03B") (pin "2") (pinfunction "~{SHDN1}_2") (pintype "bidirectional"))
    )
    (net (code "41") (name "NFB1") (class "Default")
      (node (ref "C08B") (pin "1") (pinfunction "1_1") (pintype "passive"))
      (node (ref "R13B") (pin "1") (pinfunction "1_1") (pintype "passive"))
      (node (ref "R14B") (pin "2") (pinfunction "2_2") (pintype "passive"))
      (node (ref "U03B") (pin "1") (pinfunction "NFB1_1") (pintype "bidirectional"))
    )
    (net (code "42") (name "Net-(C02B-Pad2)") (class "Default")
      (node (ref "C02B") (pin "2") (pinfunction "2_2") (pintype "passive"))
      (node (ref "J04B") (pin "2") (pinfunction "2_2") (pintype "passive"))
      (node (ref "J05B") (pin "1") (pinfunction "1_1") (pintype "passive"))
      (node (ref "U01B") (pin "2") (pinfunction "BAT_2") (pintype "bidirectional"))
      (node (ref "U01B") (pin "3") (pinfunction "BAT_3") (pintype "bidirectional"))
    )
    (net (code "43") (name "Net-(C07B-Pad2)") (class "Default")
      (node (ref "C07B") (pin "2") (pinfunction "2_2") (pintype "passive"))
      (node (ref "D03B") (pin "A") (pinfunction "A_A") (pintype "passive"))
      (node (ref "D04B") (pin "C") (pinfunction "C_C") (pintype "passive"))
    )
    (net (code "44") (name "Net-(D01B-PadA)") (class "Default")
      (node (ref "D01B") (pin "A") (pinfunction "A_A") (pintype "passive"))
      (node (ref "R01B") (pin "2") (pinfunction "2_2") (pintype "passive"))
    )
    (net (code "45") (name "Net-(D01S-PadA)") (class "Default")
      (node (ref "D01S") (pin "A") (pinfunction "A_A") (pintype "passive"))
      (node (ref "R01S") (pin "1") (pinfunction "1_1") (pintype "passive"))
    )
    (net (code "46") (name "Net-(D02B-PadA)") (class "Default")
      (node (ref "D02B") (pin "A") (pinfunction "A_A") (pintype "passive"))
      (node (ref "R02B") (pin "1") (pinfunction "1_1") (pintype "passive"))
    )
    (net (code "47") (name "Net-(D06B-PadA)") (class "Default")
      (node (ref "D06B") (pin "A") (pinfunction "A_A") (pintype "passive"))
      (node (ref "R20B") (pin "2") (pinfunction "2_2") (pintype "passive"))
    )
    (net (code "48") (name "Net-(J02S-CE1)") (class "Default")
      (node (ref "J02S") (pin "9") (pinfunction "CE1_9") (pintype "bidirectional"))
      (node (ref "R02D") (pin "1") (pinfunction "1_1") (pintype "passive"))
    )
    (net (code "49") (name "Net-(J02S-GMODE1)") (class "Default")
      (node (ref "J02S") (pin "28") (pinfunction "GMODE1_28") (pintype "bidirectional"))
      (node (ref "R04D") (pin "2") (pinfunction "2_2") (pintype "passive"))
    )
    (net (code "50") (name "Net-(J02S-RL)") (class "Default")
      (node (ref "J02S") (pin "29") (pinfunction "RL_29") (pintype "bidirectional"))
      (node (ref "SJ1") (pin "2") (pinfunction "2_2") (pintype "passive"))
    )
    (net (code "51") (name "Net-(J02S-U1CE1)") (class "Default")
      (node (ref "J02S") (pin "31") (pinfunction "U1CE1_31") (pintype "bidirectional"))
      (node (ref "R06D") (pin "2") (pinfunction "2_2") (pintype "passive"))
    )
    (net (code "52") (name "Net-(J02S-U1CE2)") (class "Default")
      (node (ref "J02S") (pin "30") (pinfunction "U1CE2_30") (pintype "bidirectional"))
      (node (ref "R05D") (pin "2") (pinfunction "2_2") (pintype "passive"))
    )
    (net (code "53") (name "Net-(J02S-U2CE1)") (class "Default")
      (node (ref "J02S") (pin "36") (pinfunction "U2CE1_36") (pintype "bidirectional"))
      (node (ref "R09D") (pin "2") (pinfunction "2_2") (pintype "passive"))
    )
    (net (code "54") (name "Net-(J02S-U2CE2)") (class "Default")
      (node (ref "J02S") (pin "35") (pinfunction "U2CE2_35") (pintype "bidirectional"))
      (node (ref "R08D") (pin "2") (pinfunction "2_2") (pintype "passive"))
    )
    (net (code "55") (name "Net-(J02S-U2CKV)") (class "Default")
      (node (ref "J02S") (pin "38") (pinfunction "U2CKV_38") (pintype "bidirectional"))
      (node (ref "R10D") (pin "1") (pinfunction "1_1") (pintype "passive"))
    )
    (net (code "56") (name "Net-(J02S-U2SPV)") (class "Default")
      (node (ref "J02S") (pin "37") (pinfunction "U2SPV_37") (pintype "bidirectional"))
      (node (ref "R11D") (pin "1") (pinfunction "1_1") (pintype "passive"))
    )
    (net (code "57") (name "Net-(J02S-VBORDER)") (class "Default")
      (node (ref "J02S") (pin "34") (pinfunction "VBORDER_34") (pintype "bidirectional"))
      (node (ref "R07D") (pin "1") (pinfunction "1_1") (pintype "passive"))
    )
    (net (code "58") (name "Net-(R18B-E)") (class "Default")
      (node (ref "R17B") (pin "1") (pinfunction "1_1") (pintype "passive"))
      (node (ref "R18B") (pin "3") (pinfunction "E_3") (pintype "passive"))
    )
    (net (code "59") (name "Net-(R18B-S)") (class "Default")
      (node (ref "R18B") (pin "2") (pinfunction "S_2") (pintype "passive"))
      (node (ref "U06B") (pin "5") (pinfunction "+IN2_5") (pintype "input"))
    )
    (net (code "60") (name "Net-(TP01B-TP)") (class "Default")
      (node (ref "R11B") (pin "1") (pinfunction "1_1") (pintype "passive"))
      (node (ref "TP01B") (pin "P$1") (pinfunction "TP_P$1") (pintype "bidirectional"))
      (node (ref "U02B") (pin "1") (pinfunction "EN_1") (pintype "bidirectional"))
    )
    (net (code "61") (name "Net-(U$1-TP)") (class "Default")
      (node (ref "U$1") (pin "P$1") (pinfunction "TP_P$1") (pintype "bidirectional"))
      (node (ref "U01M") (pin "4") (pinfunction "/RST_4") (pintype "input"))
    )
    (net (code "62") (name "Net-(U$2-TP)") (class "Default")
      (node (ref "U$2") (pin "P$1") (pinfunction "TP_P$1") (pintype "bidirectional"))
      (node (ref "U01M") (pin "7") (pinfunction "INT_7") (pintype "output"))
    )
    (net (code "63") (name "Net-(U$3-TP)") (class "Default")
      (node (ref "U$3") (pin "P$1") (pinfunction "TP_P$1") (pintype "bidirectional"))
      (node (ref "U02M") (pin "4") (pinfunction "/RST_4") (pintype "input"))
    )
    (net (code "64") (name "Net-(U$4-TP)") (class "Default")
      (node (ref "U$4") (pin "P$1") (pinfunction "TP_P$1") (pintype "bidirectional"))
      (node (ref "U02M") (pin "7") (pinfunction "INT_7") (pintype "output"))
    )
    (net (code "65") (name "Net-(U1-PROG)") (class "Default")
      (node (ref "R21B") (pin "2") (pinfunction "2_2") (pintype "passive"))
      (node (ref "U1") (pin "5") (pinfunction "PROG_5") (pintype "input"))
    )
    (net (code "66") (name "Net-(U1-STAT)") (class "Default")
      (node (ref "D06B") (pin "C") (pinfunction "C_C") (pintype "passive"))
      (node (ref "U1") (pin "1") (pinfunction "STAT_1") (pintype "output"))
    )
    (net (code "67") (name "Net-(U01B-EN1)") (class "Default")
      (node (ref "R03B") (pin "1") (pinfunction "1_1") (pintype "passive"))
      (node (ref "U01B") (pin "6") (pinfunction "EN1_6") (pintype "bidirectional"))
    )
    (net (code "68") (name "Net-(U01B-EN2)") (class "Default")
      (node (ref "R04B") (pin "1") (pinfunction "1_1") (pintype "passive"))
      (node (ref "U01B") (pin "5") (pinfunction "EN2_5") (pintype "bidirectional"))
    )
    (net (code "69") (name "Net-(U01B-ILIM)") (class "Default")
      (node (ref "R08B") (pin "2") (pinfunction "2_2") (pintype "passive"))
      (node (ref "U01B") (pin "12") (pinfunction "ILIM_12") (pintype "bidirectional"))
    )
    (net (code "70") (name "Net-(U01B-ISET)") (class "Default")
      (node (ref "R09B") (pin "2") (pinfunction "2_2") (pintype "passive"))
      (node (ref "U01B") (pin "16") (pinfunction "ISET_16") (pintype "bidirectional"))
    )
    (net (code "71") (name "Net-(U01B-TMR)") (class "Default")
      (node (ref "R06B") (pin "2") (pinfunction "2_2") (pintype "passive"))
      (node (ref "U01B") (pin "14") (pinfunction "TMR_14") (pintype "bidirectional"))
    )
    (net (code "72") (name "Net-(U01B-TS)") (class "Default")
      (node (ref "R10B") (pin "2") (pinfunction "2_2") (pintype "passive"))
      (node (ref "U01B") (pin "1") (pinfunction "TS_1") (pintype "bidirectional"))
    )
    (net (code "73") (name "Net-(U01M-A0)") (class "Default")
      (node (ref "R01M") (pin "1") (pinfunction "1_1") (pintype "passive"))
      (node (ref "U01M") (pin "3") (pinfunction "A0_3") (pintype "input"))
    )
    (net (code "74") (name "Net-(U01M-A1)") (class "Default")
      (node (ref "R02M") (pin "1") (pinfunction "1_1") (pintype "passive"))
      (node (ref "U01M") (pin "2") (pinfunction "A1_2") (pintype "input"))
    )
    (net (code "75") (name "Net-(U01M-A2)") (class "Default")
      (node (ref "R03M") (pin "1") (pinfunction "1_1") (pintype "passive"))
      (node (ref "U01M") (pin "1") (pinfunction "A2_1") (pintype "input"))
    )
    (net (code "76") (name "Net-(U01S-CS)") (class "Default")
      (node (ref "C02S") (pin "1") (pinfunction "1_1") (pintype "passive"))
      (node (ref "C03S") (pin "1") (pinfunction "1_1") (pintype "passive"))
      (node (ref "C04S") (pin "1") (pinfunction "1_1") (pintype "passive"))
      (node (ref "U01S") (pin "1") (pinfunction "VDD_1") (pintype "bidirectional"))
      (node (ref "U01S") (pin "6") (pinfunction "VS_6") (pintype "bidirectional"))
      (node (ref "U01S") (pin "7") (pinfunction "CS_7") (pintype "bidirectional"))
    )
    (net (code "77") (name "Net-(U01S-INT1)") (class "Default")
      (node (ref "R02S") (pin "2") (pinfunction "2_2") (pintype "passive"))
      (node (ref "U01S") (pin "8") (pinfunction "INT1_8") (pintype "bidirectional"))
    )
    (net (code "78") (name "Net-(U02B-LX)") (class "Default")
      (node (ref "L01B") (pin "1") (pinfunction "1_1") (pintype "passive"))
      (node (ref "U02B") (pin "3") (pinfunction "LX_3") (pintype "bidirectional"))
    )
    (net (code "79") (name "Net-(U02M-A0)") (class "Default")
      (node (ref "R04M") (pin "1") (pinfunction "1_1") (pintype "passive"))
      (node (ref "U02M") (pin "3") (pinfunction "A0_3") (pintype "input"))
    )
    (net (code "80") (name "Net-(U02M-A1)") (class "Default")
      (node (ref "R05M") (pin "1") (pinfunction "1_1") (pintype "passive"))
      (node (ref "U02M") (pin "2") (pinfunction "A1_2") (pintype "input"))
    )
    (net (code "81") (name "Net-(U02M-A2)") (class "Default")
      (node (ref "R06M") (pin "1") (pinfunction "1_1") (pintype "passive"))
      (node (ref "U02M") (pin "1") (pinfunction "A2_1") (pintype "input"))
    )
    (net (code "82") (name "Net-(U03B-SW1)") (class "Default")
      (node (ref "C07B") (pin "1") (pinfunction "1_1") (pintype "passive"))
      (node (ref "L02B") (pin "P$2") (pinfunction "P$2_P$2") (pintype "bidirectional"))
      (node (ref "U03B") (pin "10") (pinfunction "SW1_10") (pintype "bidirectional"))
    )
    (net (code "83") (name "Net-(U03B-SW2)") (class "Default")
      (node (ref "D05B") (pin "A") (pinfunction "A_A") (pintype "passive"))
      (node (ref "L03B") (pin "P$2") (pinfunction "P$2_P$2") (pintype "bidirectional"))
      (node (ref "U03B") (pin "6") (pinfunction "SW2_6") (pintype "bidirectional"))
    )
    (net (code "84") (name "OE") (class "Default")
      (node (ref "J02S") (pin "7") (pinfunction "OE_7") (pintype "bidirectional"))
      (node (ref "U02M") (pin "11") (pinfunction "GP2_11") (pintype "bidirectional"))
    )
    (net (code "85") (name "POS_EN") (class "Default")
      (node (ref "U02M") (pin "16") (pinfunction "GP7_16") (pintype "bidirectional"))
      (node (ref "U03B") (pin "4") (pinfunction "~{SHDN2}_4") (pintype "bidirectional"))
    )
    (net (code "86") (name "SCL") (class "Default")
      (node (ref "R08M") (pin "2") (pinfunction "2_2") (pintype "passive"))
      (node (ref "U01M") (pin "19") (pinfunction "SCL_19") (pintype "bidirectional"))
      (node (ref "U01S") (pin "14") (pinfunction "SCL_14") (pintype "bidirectional"))
      (node (ref "U02M") (pin "19") (pinfunction "SCL_19") (pintype "bidirectional"))
      (node (ref "U03M") (pin "#14") (pinfunction "D1_#14") (pintype "bidirectional"))
      (node (ref "U03M") (pin "14") (pinfunction "D1_14") (pintype "bidirectional"))
      (node (ref "U03M") (pin "@14") (pinfunction "D1_@14") (pintype "bidirectional"))
    )
    (net (code "87") (name "SDA") (class "Default")
      (node (ref "R09M") (pin "2") (pinfunction "2_2") (pintype "passive"))
      (node (ref "U01M") (pin "20") (pinfunction "SDA_20") (pintype "bidirectional"))
      (node (ref "U01S") (pin "13") (pinfunction "SDA_13") (pintype "bidirectional"))
      (node (ref "U02M") (pin "20") (pinfunction "SDA_20") (pintype "bidirectional"))
      (node (ref "U03M") (pin "#13") (pinfunction "D0_#13") (pintype "bidirectional"))
      (node (ref "U03M") (pin "13") (pinfunction "D0_13") (pintype "bidirectional"))
      (node (ref "U03M") (pin "@13") (pinfunction "D0_@13") (pintype "bidirectional"))
    )
    (net (code "88") (name "SD_CD") (class "Default")
      (node (ref "J01S") (pin "CD1") (pinfunction "CARD_DETECT_CD1") (pintype "passive"))
      (node (ref "U$5") (pin "P$1") (pinfunction "TP_P$1") (pintype "bidirectional"))
    )
    (net (code "89") (name "SHR") (class "Default")
      (node (ref "J02S") (pin "8") (pinfunction "SHR_8") (pintype "bidirectional"))
      (node (ref "R01D") (pin "2") (pinfunction "2_2") (pintype "passive"))
      (node (ref "R03D") (pin "1") (pinfunction "1_1") (pintype "passive"))
    )
    (net (code "90") (name "SMPS_CTRL") (class "Default")
      (node (ref "Q01B") (pin "1") (pinfunction "G_1") (pintype "passive"))
      (node (ref "R12B") (pin "1") (pinfunction "1_1") (pintype "passive"))
      (node (ref "U02M") (pin "15") (pinfunction "GP6_15") (pintype "bidirectional"))
    )
    (net (code "91") (name "SPH") (class "Default")
      (node (ref "J02S") (pin "11") (pinfunction "SPH_11") (pintype "bidirectional"))
      (node (ref "U02M") (pin "12") (pinfunction "GP3_12") (pintype "bidirectional"))
    )
    (net (code "92") (name "SPI_CS") (class "Default")
      (node (ref "D01S") (pin "C") (pinfunction "C_C") (pintype "passive"))
      (node (ref "J01S") (pin "2") (pinfunction "CS_2") (pintype "input"))
      (node (ref "U03M") (pin "#10") (pinfunction "A2_#10") (pintype "bidirectional"))
      (node (ref "U03M") (pin "10") (pinfunction "A2_10") (pintype "bidirectional"))
      (node (ref "U03M") (pin "@10") (pinfunction "A2_@10") (pintype "bidirectional"))
    )
    (net (code "93") (name "SPI_MISO") (class "Default")
      (node (ref "J01S") (pin "7") (pinfunction "DATA_OUT_7") (pintype "output"))
      (node (ref "U03M") (pin "#8") (pinfunction "A4_#8") (pintype "bidirectional"))
      (node (ref "U03M") (pin "8") (pinfunction "A4_8") (pintype "bidirectional"))
      (node (ref "U03M") (pin "@8") (pinfunction "A4_@8") (pintype "bidirectional"))
    )
    (net (code "94") (name "SPI_MOSI") (class "Default")
      (node (ref "J01S") (pin "3") (pinfunction "DATA_IN_3") (pintype "input"))
      (node (ref "U03M") (pin "#7") (pinfunction "A5_#7") (pintype "bidirectional"))
      (node (ref "U03M") (pin "7") (pinfunction "A5_7") (pintype "bidirectional"))
      (node (ref "U03M") (pin "@7") (pinfunction "A5_@7") (pintype "bidirectional"))
    )
    (net (code "95") (name "SPI_SCK") (class "Default")
      (node (ref "J01S") (pin "5") (pinfunction "SCLK_5") (pintype "input"))
      (node (ref "R01S") (pin "2") (pinfunction "2_2") (pintype "passive"))
      (node (ref "U03M") (pin "#9") (pinfunction "A3_#9") (pintype "bidirectional"))
      (node (ref "U03M") (pin "9") (pinfunction "A3_9") (pintype "bidirectional"))
      (node (ref "U03M") (pin "@9") (pinfunction "A3_@9") (pintype "bidirectional"))
    )
    (net (code "96") (name "U1CKV") (class "Default")
      (node (ref "J02S") (pin "33") (pinfunction "U1CKV_33") (pintype "bidirectional"))
      (node (ref "R10D") (pin "2") (pinfunction "2_2") (pintype "passive"))
      (node (ref "U03M") (pin "#18") (pinfunction "D5_#18") (pintype "bidirectional"))
      (node (ref "U03M") (pin "18") (pinfunction "D5_18") (pintype "bidirectional"))
      (node (ref "U03M") (pin "@18") (pinfunction "D5_@18") (pintype "bidirectional"))
    )
    (net (code "97") (name "U1SPV") (class "Default")
      (node (ref "J02S") (pin "32") (pinfunction "U1SPV_32") (pintype "bidirectional"))
      (node (ref "R11D") (pin "2") (pinfunction "2_2") (pintype "passive"))
      (node (ref "U03M") (pin "#17") (pinfunction "D4_#17") (pintype "bidirectional"))
      (node (ref "U03M") (pin "17") (pinfunction "D4_17") (pintype "bidirectional"))
      (node (ref "U03M") (pin "@17") (pinfunction "D4_@17") (pintype "bidirectional"))
    )
    (net (code "98") (name "VBUS") (class "Default")
      (node (ref "C01B") (pin "2") (pinfunction "2_2") (pintype "passive"))
      (node (ref "C19B") (pin "2") (pinfunction "2_2") (pintype "passive"))
      (node (ref "J01B") (pin "1") (pinfunction "1_1") (pintype "passive"))
      (node (ref "J07B") (pin "VBUS") (pinfunction "VBUS_VBUS") (pintype "bidirectional"))
      (node (ref "R20B") (pin "1") (pinfunction "1_1") (pintype "passive"))
      (node (ref "U01B") (pin "13") (pinfunction "IN_13") (pintype "bidirectional"))
      (node (ref "U1") (pin "4") (pinfunction "VIN_4") (pintype "power_in"))
    )
    (net (code "99") (name "VCOM") (class "Default")
      (node (ref "C17B") (pin "2") (pinfunction "2_2") (pintype "passive"))
      (node (ref "J02S") (pin "22") (pinfunction "VCOM_22") (pintype "bidirectional"))
      (node (ref "J13B") (pin "1") (pinfunction "1_1") (pintype "passive"))
      (node (ref "U06B") (pin "6") (pinfunction "-IN2_6") (pintype "input"))
      (node (ref "U06B") (pin "7") (pinfunction "OUT2_7") (pintype "output"))
    )
    (net (code "100") (name "VIN") (class "Default")
      (node (ref "C09B") (pin "2") (pinfunction "2_2") (pintype "passive"))
      (node (ref "J08B") (pin "1") (pinfunction "1_1") (pintype "passive"))
      (node (ref "L02B") (pin "P$1") (pinfunction "P$1_P$1") (pintype "bidirectional"))
      (node (ref "L03B") (pin "P$1") (pinfunction "P$1_P$1") (pintype "bidirectional"))
      (node (ref "Q01B") (pin "3") (pinfunction "D_3") (pintype "passive"))
      (node (ref "U03B") (pin "8") (pinfunction "VIN_8") (pintype "bidirectional"))
    )
    (net (code "101") (name "unconnected-(J01M-Pad2)") (class "Default")
      (node (ref "J01M") (pin "2") (pinfunction "2_2") (pintype "passive"))
    )
    (net (code "102") (name "unconnected-(J01S-CARD_DETECT1-PadCD2)") (class "Default")
      (node (ref "J01S") (pin "CD2") (pinfunction "CARD_DETECT1_CD2") (pintype "passive"))
    )
    (net (code "103") (name "unconnected-(J01S-DAT1-Pad8)") (class "Default")
      (node (ref "J01S") (pin "8") (pinfunction "DAT1_8") (pintype "bidirectional"))
    )
    (net (code "104") (name "unconnected-(J01S-DAT2-Pad1)") (class "Default")
      (node (ref "J01S") (pin "1") (pinfunction "DAT2_1") (pintype "bidirectional"))
    )
    (net (code "105") (name "unconnected-(J02S-NC-20-Pad20)") (class "Default")
      (node (ref "J02S") (pin "20") (pinfunction "NC-20_20") (pintype "bidirectional"))
    )
    (net (code "106") (name "unconnected-(J02S-NC-21-Pad21)") (class "Default")
      (node (ref "J02S") (pin "21") (pinfunction "NC-21_21") (pintype "bidirectional"))
    )
    (net (code "107") (name "unconnected-(J02S-NC-25-Pad25)") (class "Default")
      (node (ref "J02S") (pin "25") (pinfunction "NC-25_25") (pintype "bidirectional"))
    )
    (net (code "108") (name "unconnected-(J02S-NC-26-Pad26)") (class "Default")
      (node (ref "J02S") (pin "26") (pinfunction "NC-26_26") (pintype "bidirectional"))
    )
    (net (code "109") (name "unconnected-(J02S-NC-39-Pad39)") (class "Default")
      (node (ref "J02S") (pin "39") (pinfunction "NC-39_39") (pintype "bidirectional"))
    )
    (net (code "110") (name "unconnected-(J03B-PAD1-PadNC1)") (class "Default")
      (node (ref "J03B") (pin "NC1") (pinfunction "PAD1_NC1") (pintype "bidirectional"))
    )
    (net (code "111") (name "unconnected-(J03B-PAD2-PadNC2)") (class "Default")
      (node (ref "J03B") (pin "NC2") (pinfunction "PAD2_NC2") (pintype "bidirectional"))
    )
    (net (code "112") (name "unconnected-(U01S-INT2-Pad9)") (class "Default")
      (node (ref "U01S") (pin "9") (pinfunction "INT2_9") (pintype "bidirectional"))
    )
    (net (code "113") (name "unconnected-(U01S-NC-Pad3)") (class "Default")
      (node (ref "U01S") (pin "3") (pinfunction "NC_3") (pintype "bidirectional"))
    )
    (net (code "114") (name "unconnected-(U01S-NC-Pad10)") (class "Default")
      (node (ref "U01S") (pin "10") (pinfunction "NC_10") (pintype "bidirectional"))
    )
    (net (code "115") (name "unconnected-(U01S-NC-Pad11)") (class "Default")
      (node (ref "U01S") (pin "11") (pinfunction "NC_11") (pintype "bidirectional"))
    )
    (net (code "116") (name "unconnected-(U04B-NC-Pad4)") (class "Default")
      (node (ref "U04B") (pin "4") (pinfunction "NC_4") (pintype "bidirectional"))
    )
    (net (code "117") (name "unconnected-(U04B-NC-Pad8)") (class "Default")
      (node (ref "U04B") (pin "8") (pinfunction "NC_8") (pintype "bidirectional"))
    )
    (net (code "118") (name "unconnected-(U05B-NC-Pad4)") (class "Default")
      (node (ref "U05B") (pin "4") (pinfunction "NC_4") (pintype "bidirectional"))
    )
    (net (code "119") (name "unconnected-(U05B-NC-Pad5)") (class "Default")
      (node (ref "U05B") (pin "5") (pinfunction "NC_5") (pintype "bidirectional"))
    )
    (net (code "120") (name "unconnected-(U06B-+IN1-Pad3)") (class "Default")
      (node (ref "U06B") (pin "3") (pinfunction "+IN1_3") (pintype "input"))
    )
    (net (code "121") (name "unconnected-(U06B--IN1-Pad2)") (class "Default")
      (node (ref "U06B") (pin "2") (pinfunction "-IN1_2") (pintype "input"))
    )
    (net (code "122") (name "unconnected-(U06B-OUT1-Pad1)") (class "Default")
      (node (ref "U06B") (pin "1") (pinfunction "OUT1_1") (pintype "output"))
    )
  )
)
